# miniSpartan6__Rev_B.net
KiCad netlist of a schematic drawn in EAGLE
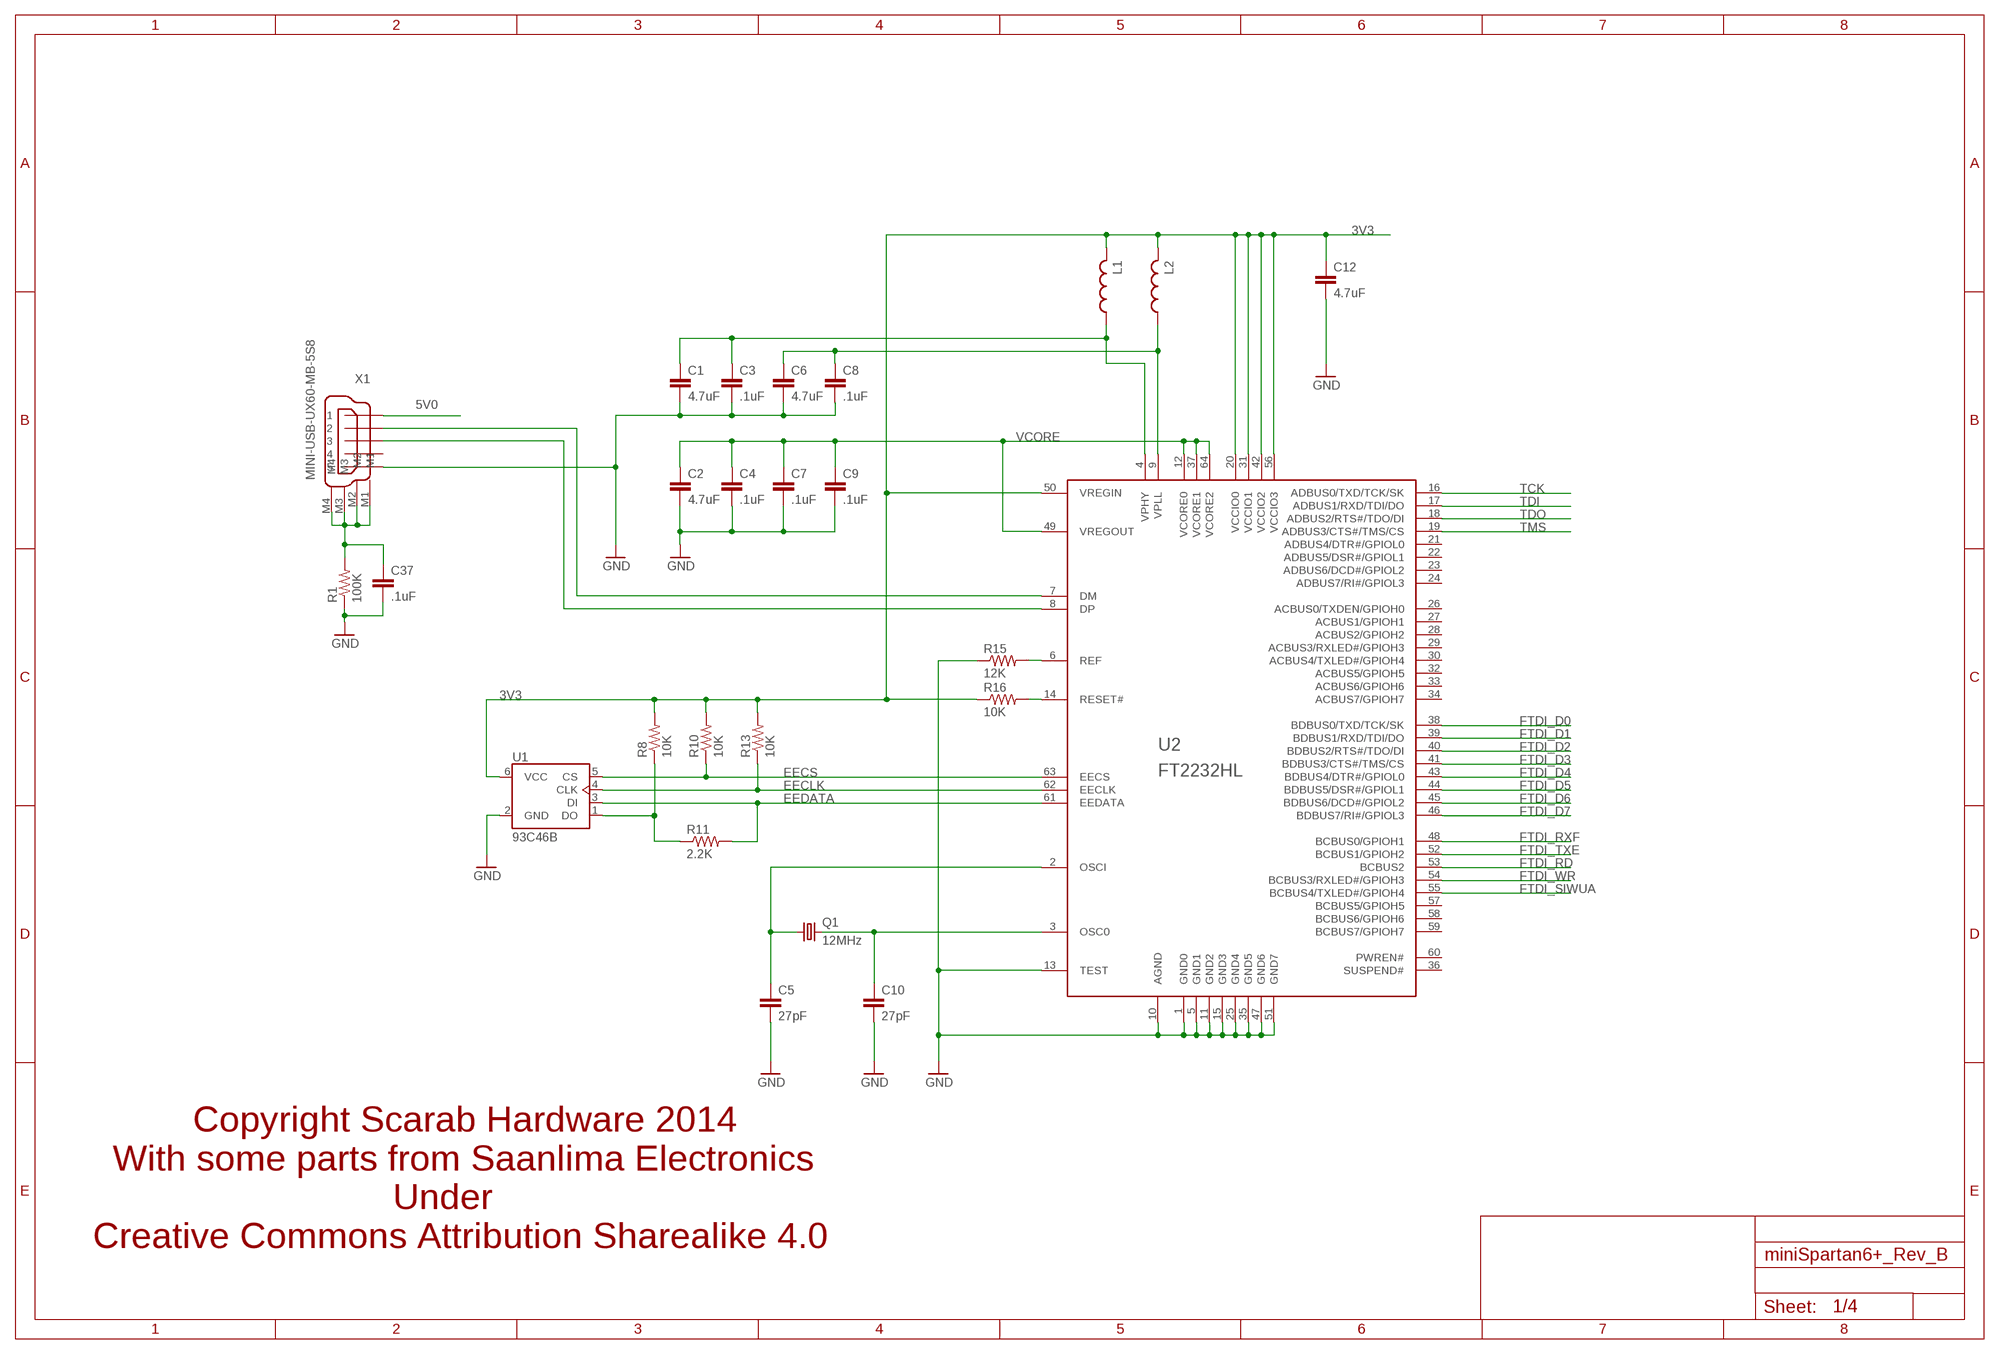
[diagram p0: schematic, sheet 1]
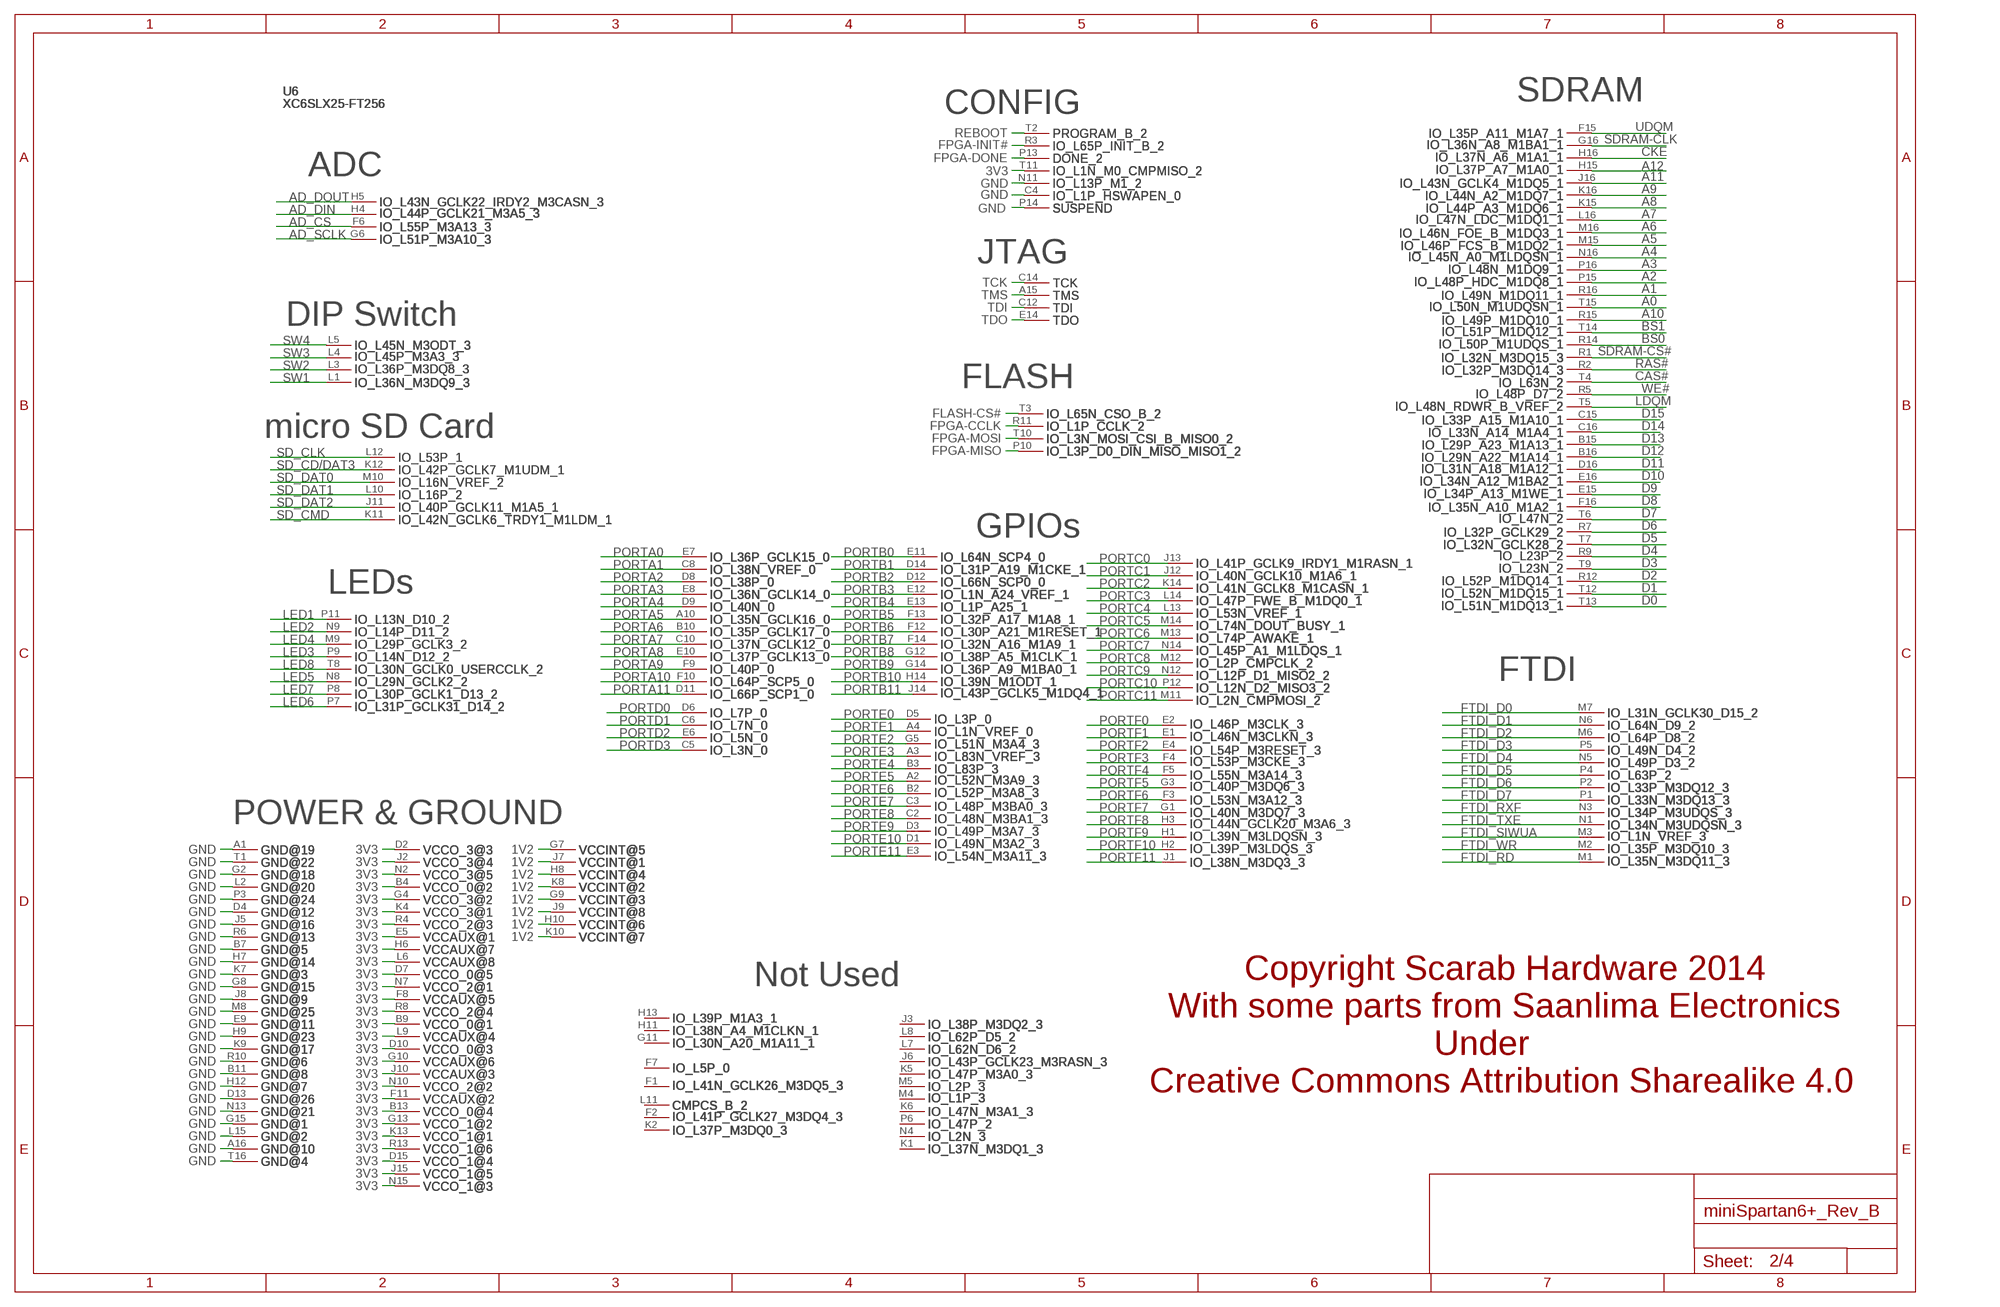
[diagram p1: schematic, sheet 2]
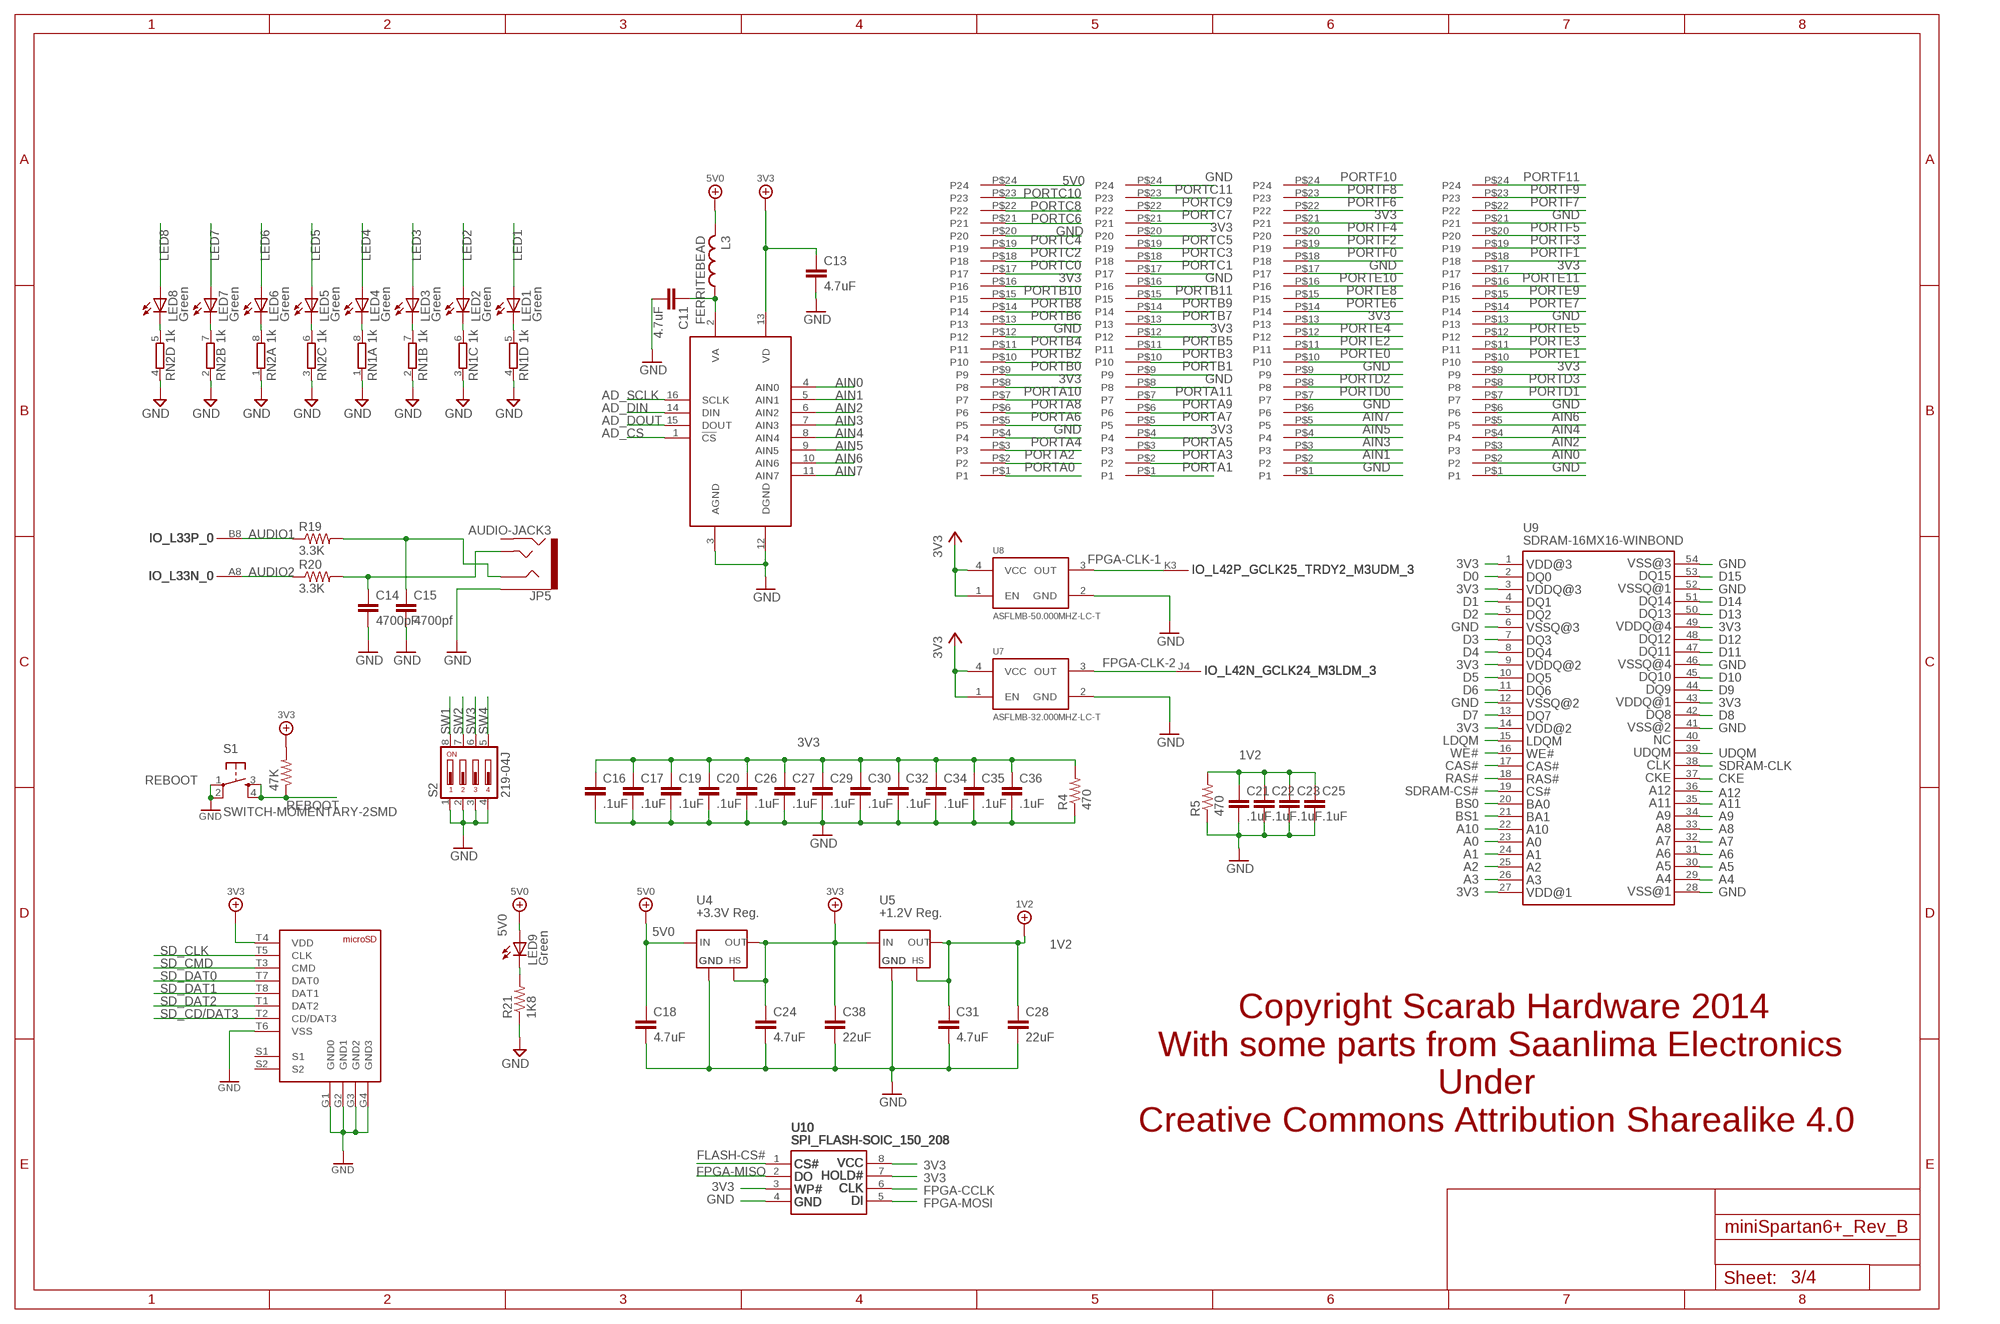
[diagram p2: schematic, sheet 3]
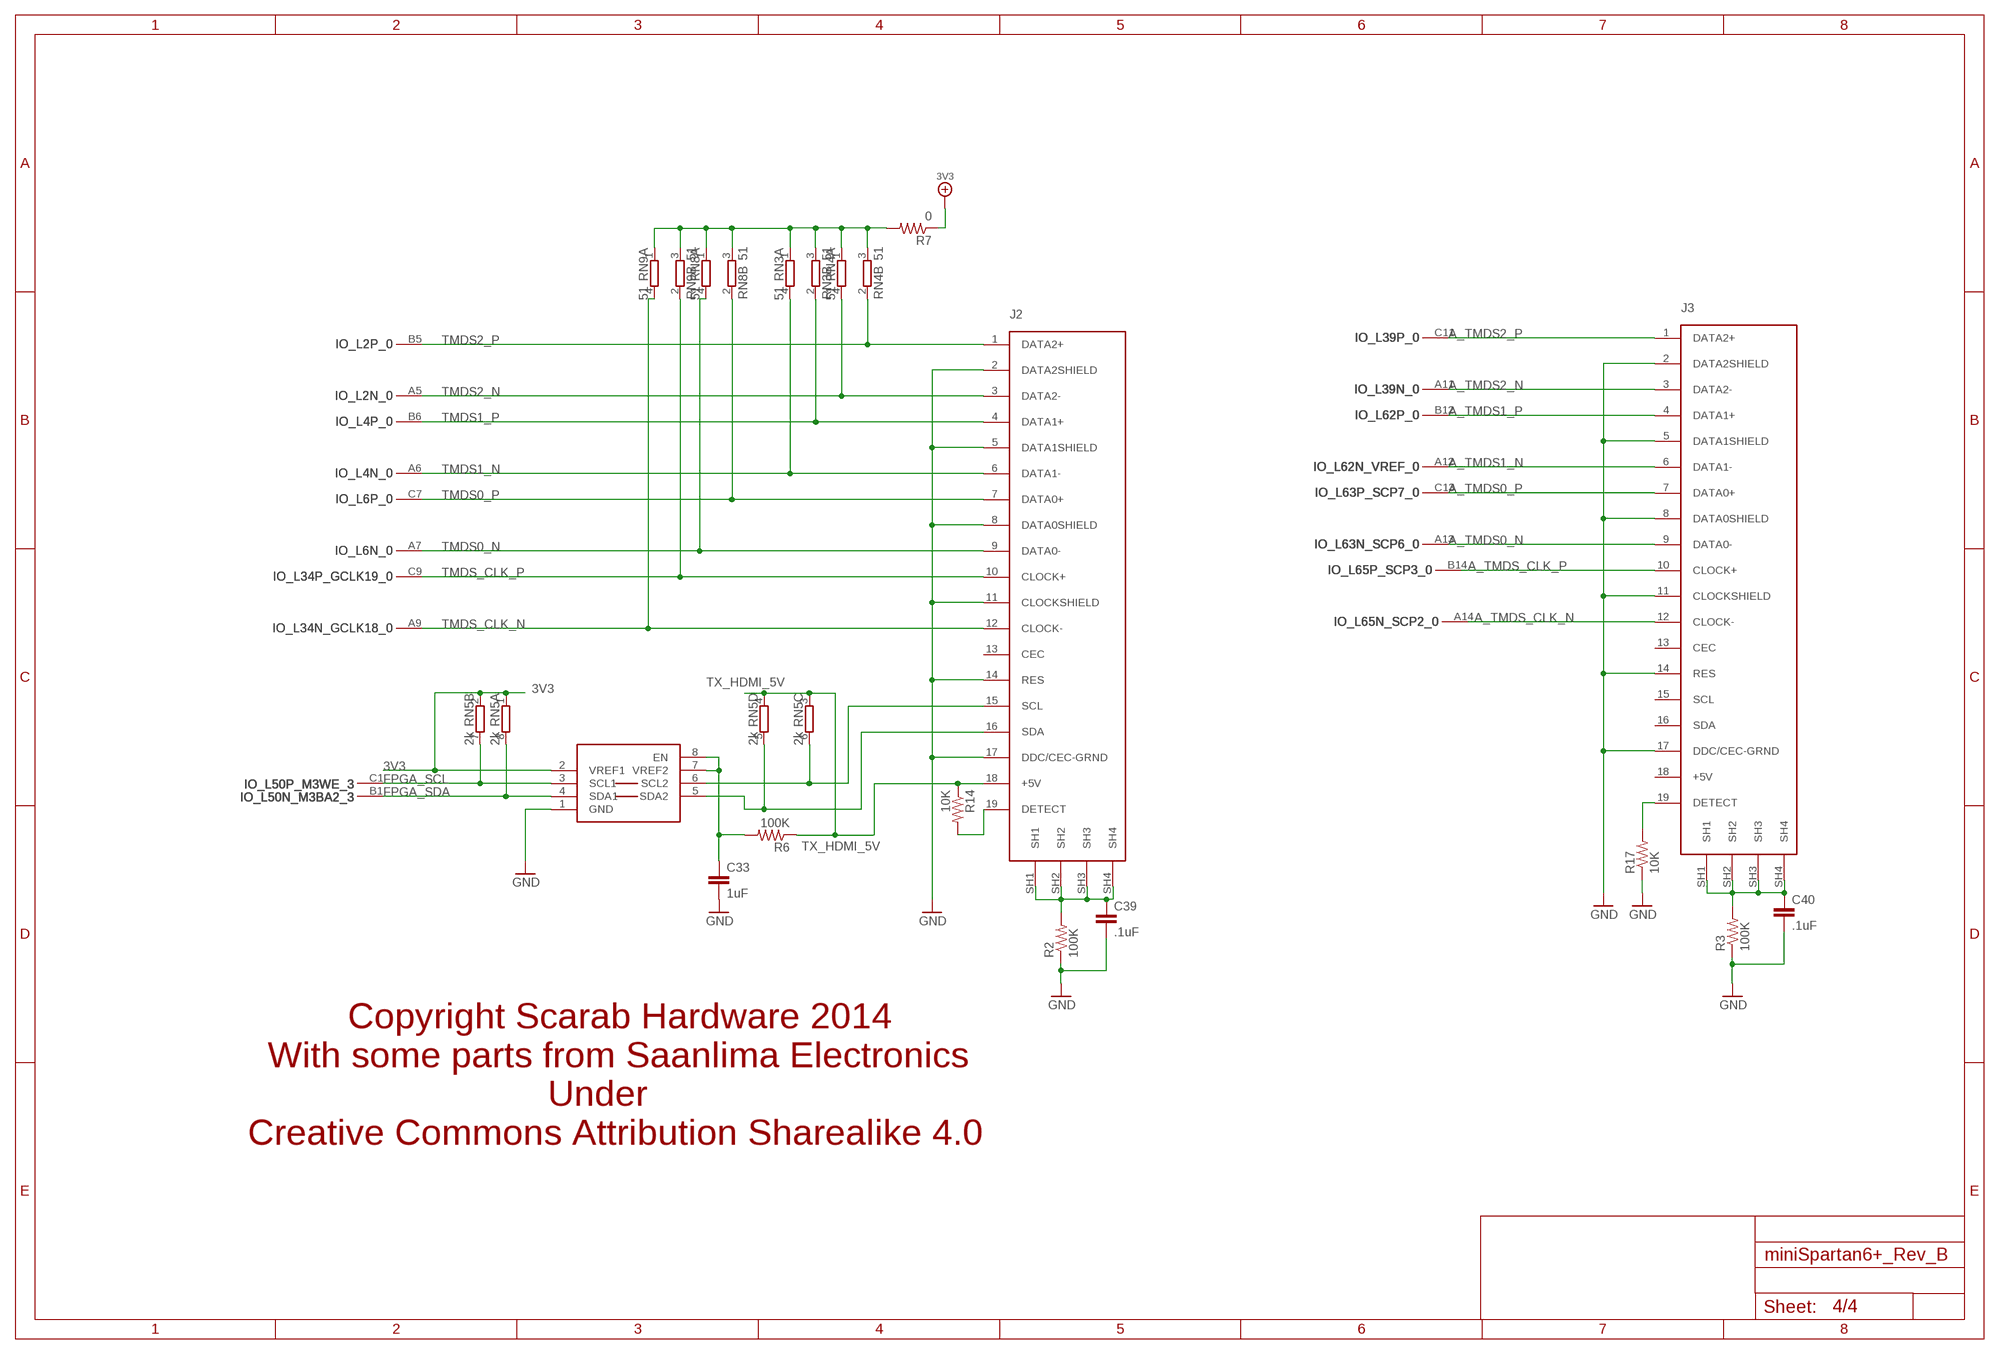
[diagram p3: schematic, sheet 4]

(export (version "E")
  (design (tool "Eeschema 10.0.6"))
  (components
    (comp (ref "C1")
      (value "4.7uF")
      (footprint "eagle-import:C0603K")
      (libsource (lib "eagle-import") (part "C-EUC0603K"))
    )
    (comp (ref "C2")
      (value "4.7uF")
      (footprint "eagle-import:C0603K")
      (libsource (lib "eagle-import") (part "C-EUC0603K"))
    )
    (comp (ref "C3")
      (value ".1uF")
      (footprint "eagle-import:C0603K")
      (libsource (lib "eagle-import") (part "C-EUC0603K"))
    )
    (comp (ref "C4")
      (value ".1uF")
      (footprint "eagle-import:C0603K")
      (libsource (lib "eagle-import") (part "C-EUC0603K"))
    )
    (comp (ref "C5")
      (value "27pF")
      (footprint "eagle-import:C0603K")
      (libsource (lib "eagle-import") (part "C-EUC0603K"))
    )
    (comp (ref "C6")
      (value "4.7uF")
      (footprint "eagle-import:C0603K")
      (libsource (lib "eagle-import") (part "C-EUC0603K"))
    )
    (comp (ref "C7")
      (value ".1uF")
      (footprint "eagle-import:C0603K")
      (libsource (lib "eagle-import") (part "C-EUC0603K"))
    )
    (comp (ref "C8")
      (value ".1uF")
      (footprint "eagle-import:C0603K")
      (libsource (lib "eagle-import") (part "C-EUC0603K"))
    )
    (comp (ref "C9")
      (value ".1uF")
      (footprint "eagle-import:C0603K")
      (libsource (lib "eagle-import") (part "C-EUC0603K"))
    )
    (comp (ref "C10")
      (value "27pF")
      (footprint "eagle-import:C0603K")
      (libsource (lib "eagle-import") (part "C-EUC0603K"))
    )
    (comp (ref "C12")
      (value "4.7uF")
      (footprint "eagle-import:C0603K")
      (libsource (lib "eagle-import") (part "C-EUC0603K"))
    )
    (comp (ref "C37")
      (value ".1uF")
      (footprint "eagle-import:C0603K")
      (libsource (lib "eagle-import") (part "C-EUC0603K"))
    )
    (comp (ref "L1")
      (value "L-USL2012C")
      (footprint "eagle-import:L2012C")
      (libsource (lib "eagle-import") (part "L-USL2012C"))
    )
    (comp (ref "L2")
      (value "L-USL2012C")
      (footprint "eagle-import:L2012C")
      (libsource (lib "eagle-import") (part "L-USL2012C"))
    )
    (comp (ref "Q1")
      (value "12MHz")
      (footprint "eagle-import:CRYSTAL3.2X2.5MM")
      (libsource (lib "eagle-import") (part "CRYSTAL3.2X2.5"))
    )
    (comp (ref "R1")
      (value "100K")
      (footprint "eagle-import:R0603")
      (libsource (lib "eagle-import") (part "R-US_R0603"))
    )
    (comp (ref "R8")
      (value "10K")
      (footprint "eagle-import:R0603")
      (libsource (lib "eagle-import") (part "R-US_R0603"))
    )
    (comp (ref "R10")
      (value "10K")
      (footprint "eagle-import:R0603")
      (libsource (lib "eagle-import") (part "R-US_R0603"))
    )
    (comp (ref "R11")
      (value "2.2K")
      (footprint "eagle-import:R0603")
      (libsource (lib "eagle-import") (part "R-US_R0603"))
    )
    (comp (ref "R13")
      (value "10K")
      (footprint "eagle-import:R0603")
      (libsource (lib "eagle-import") (part "R-US_R0603"))
    )
    (comp (ref "R15")
      (value "12K")
      (footprint "eagle-import:R0603")
      (libsource (lib "eagle-import") (part "R-US_R0603"))
    )
    (comp (ref "R16")
      (value "10K")
      (footprint "eagle-import:R0603")
      (libsource (lib "eagle-import") (part "R-US_R0603"))
    )
    (comp (ref "U1")
      (value "93C46B")
      (footprint "eagle-import:SOT23-6")
      (libsource (lib "eagle-import") (part "DIGITAL-EEPROM-MICROWIRE-6P_SOT23"))
    )
    (comp (ref "U2")
      (value "FT2232HL")
      (footprint "eagle-import:LQFP64")
      (libsource (lib "eagle-import") (part "FT2232H"))
    )
    (comp (ref "X1")
      (value "MINI-USB-UX60-MB-5S8")
      (footprint "eagle-import:UX60-MB-5S8")
      (libsource (lib "eagle-import") (part "MINI-USB-UX60-MB-5S8"))
    )
    (comp (ref "C33")
      (value "1uF")
      (footprint "eagle-import:C0603K")
      (libsource (lib "eagle-import") (part "C-EUC0603K"))
    )
    (comp (ref "C39")
      (value ".1uF")
      (footprint "eagle-import:C0603K")
      (libsource (lib "eagle-import") (part "C-EUC0603K"))
    )
    (comp (ref "C40")
      (value ".1uF")
      (footprint "eagle-import:C0603K")
      (libsource (lib "eagle-import") (part "C-EUC0603K"))
    )
    (comp (ref "J2")
      (value "HDMI-TYPE-A-RECEPTICALFCI10029449")
      (footprint "eagle-import:FCI-HDMI-TYPE-A-RECEPT")
      (libsource (lib "eagle-import") (part "HDMI-TYPE-A-RECEPTICALFCI10029449"))
    )
    (comp (ref "J3")
      (value "HDMI-TYPE-A-RECEPTICALFCI10029449")
      (footprint "eagle-import:FCI-HDMI-TYPE-A-RECEPT")
      (libsource (lib "eagle-import") (part "HDMI-TYPE-A-RECEPTICALFCI10029449"))
    )
    (comp (ref "R2")
      (value "100K")
      (footprint "eagle-import:R0603")
      (libsource (lib "eagle-import") (part "R-US_R0603"))
    )
    (comp (ref "R3")
      (value "100K")
      (footprint "eagle-import:R0603")
      (libsource (lib "eagle-import") (part "R-US_R0603"))
    )
    (comp (ref "R6")
      (value "100K")
      (footprint "eagle-import:R0603")
      (libsource (lib "eagle-import") (part "R-US_R0603"))
    )
    (comp (ref "R7")
      (value "0")
      (footprint "eagle-import:R0603")
      (libsource (lib "eagle-import") (part "R-US_R0603"))
    )
    (comp (ref "R14")
      (value "10K")
      (footprint "eagle-import:R0603")
      (libsource (lib "eagle-import") (part "R-US_R0603"))
    )
    (comp (ref "R17")
      (value "10K")
      (footprint "eagle-import:R0603")
      (libsource (lib "eagle-import") (part "R-US_R0603"))
    )
    (comp (ref "RN3")
      (value "51")
      (footprint "eagle-import:EXB34V")
      (libsource (lib "eagle-import") (part "2R-NEXB34V"))
    )
    (comp (ref "RN4")
      (value "51")
      (footprint "eagle-import:EXB34V")
      (libsource (lib "eagle-import") (part "2R-NEXB34V"))
    )
    (comp (ref "RN5")
      (value "2k")
      (footprint "eagle-import:0603-ARV")
      (libsource (lib "eagle-import") (part "4R-N0603-ARV"))
    )
    (comp (ref "RN8")
      (value "51")
      (footprint "eagle-import:EXB34V")
      (libsource (lib "eagle-import") (part "2R-NEXB34V"))
    )
    (comp (ref "RN9")
      (value "51")
      (footprint "eagle-import:EXB34V")
      (libsource (lib "eagle-import") (part "2R-NEXB34V"))
    )
    (comp (ref "U6")
      (value "XC6SLX25-FT256")
      (footprint "eagle-import:XILINX-FT256")
      (fields
        (field (name "DIGIKEY#") "122-1753-ND")
        (field (name "MANF") "XILINX")
        (field (name "MANF#") "XC6SLX25-2FTG256C")
      )
      (libsource (lib "eagle-import") (part "XC6SLX25-FT256"))
    )
    (comp (ref "U11")
      (value "PCA9306")
      (footprint "eagle-import:PSOP-8")
      (libsource (lib "eagle-import") (part "PCA9306"))
    )
    (comp (ref "C11")
      (value "4.7uF")
      (footprint "eagle-import:C0603K")
      (libsource (lib "eagle-import") (part "C-EUC0603K"))
    )
    (comp (ref "C13")
      (value "4.7uF")
      (footprint "eagle-import:C0603K")
      (libsource (lib "eagle-import") (part "C-EUC0603K"))
    )
    (comp (ref "C14")
      (value "4700pF")
      (footprint "eagle-import:C0603K")
      (libsource (lib "eagle-import") (part "C-EUC0603K"))
    )
    (comp (ref "C15")
      (value "4700pf")
      (footprint "eagle-import:C0603K")
      (libsource (lib "eagle-import") (part "C-EUC0603K"))
    )
    (comp (ref "C16")
      (value ".1uF")
      (footprint "eagle-import:C0603K")
      (libsource (lib "eagle-import") (part "C-EUC0603K"))
    )
    (comp (ref "C17")
      (value ".1uF")
      (footprint "eagle-import:C0603K")
      (libsource (lib "eagle-import") (part "C-EUC0603K"))
    )
    (comp (ref "C18")
      (value "4.7uF")
      (footprint "eagle-import:C0603K")
      (fields (field (name "MANF") "Murata"))
      (libsource (lib "eagle-import") (part "C-EUC0603K"))
    )
    (comp (ref "C19")
      (value ".1uF")
      (footprint "eagle-import:C0603K")
      (libsource (lib "eagle-import") (part "C-EUC0603K"))
    )
    (comp (ref "C20")
      (value ".1uF")
      (footprint "eagle-import:C0603K")
      (libsource (lib "eagle-import") (part "C-EUC0603K"))
    )
    (comp (ref "C21")
      (value ".1uF")
      (footprint "eagle-import:C0603K")
      (libsource (lib "eagle-import") (part "C-EUC0603K"))
    )
    (comp (ref "C22")
      (value ".1uF")
      (footprint "eagle-import:C0603K")
      (libsource (lib "eagle-import") (part "C-EUC0603K"))
    )
    (comp (ref "C23")
      (value ".1uF")
      (footprint "eagle-import:C0603K")
      (libsource (lib "eagle-import") (part "C-EUC0603K"))
    )
    (comp (ref "C24")
      (value "4.7uF")
      (footprint "eagle-import:C0603K")
      (fields (field (name "MANF") "Murata"))
      (libsource (lib "eagle-import") (part "C-EUC0603K"))
    )
    (comp (ref "C25")
      (value ".1uF")
      (footprint "eagle-import:C0603K")
      (libsource (lib "eagle-import") (part "C-EUC0603K"))
    )
    (comp (ref "C26")
      (value ".1uF")
      (footprint "eagle-import:C0603K")
      (libsource (lib "eagle-import") (part "C-EUC0603K"))
    )
    (comp (ref "C27")
      (value ".1uF")
      (footprint "eagle-import:C0603K")
      (libsource (lib "eagle-import") (part "C-EUC0603K"))
    )
    (comp (ref "C28")
      (value "22uF")
      (footprint "eagle-import:C0603K")
      (fields (field (name "MANF") "Murata"))
      (libsource (lib "eagle-import") (part "C-EUC0603K"))
    )
    (comp (ref "C29")
      (value ".1uF")
      (footprint "eagle-import:C0603K")
      (libsource (lib "eagle-import") (part "C-EUC0603K"))
    )
    (comp (ref "C30")
      (value ".1uF")
      (footprint "eagle-import:C0603K")
      (libsource (lib "eagle-import") (part "C-EUC0603K"))
    )
    (comp (ref "C31")
      (value "4.7uF")
      (footprint "eagle-import:C0603K")
      (fields (field (name "MANF") "Murata"))
      (libsource (lib "eagle-import") (part "C-EUC0603K"))
    )
    (comp (ref "C32")
      (value ".1uF")
      (footprint "eagle-import:C0603K")
      (libsource (lib "eagle-import") (part "C-EUC0603K"))
    )
    (comp (ref "C34")
      (value ".1uF")
      (footprint "eagle-import:C0603K")
      (libsource (lib "eagle-import") (part "C-EUC0603K"))
    )
    (comp (ref "C35")
      (value ".1uF")
      (footprint "eagle-import:C0603K")
      (libsource (lib "eagle-import") (part "C-EUC0603K"))
    )
    (comp (ref "C36")
      (value ".1uF")
      (footprint "eagle-import:C0603K")
      (libsource (lib "eagle-import") (part "C-EUC0603K"))
    )
    (comp (ref "C38")
      (value "22uF")
      (footprint "eagle-import:C0603K")
      (fields (field (name "MANF") "Murata"))
      (libsource (lib "eagle-import") (part "C-EUC0603K"))
    )
    (comp (ref "J4")
      (value "P24-1")
      (footprint "eagle-import:1X24")
      (libsource (lib "eagle-import") (part "P24-1"))
    )
    (comp (ref "J5")
      (value "MICROSD_MOLEX")
      (footprint "eagle-import:MICROSD_104031")
      (libsource (lib "eagle-import") (part "MICROSD_MOLEX"))
    )
    (comp (ref "J6")
      (value "P24-1")
      (footprint "eagle-import:1X24")
      (libsource (lib "eagle-import") (part "P24-1"))
    )
    (comp (ref "JP5")
      (value "AUDIO-JACK3")
      (footprint "eagle-import:AUDIO-JACK-TRRS-SMD")
      (libsource (lib "eagle-import") (part "AUDIO-JACK3"))
    )
    (comp (ref "L3")
      (value "FERRITEBEAD")
      (footprint "eagle-import:L2012C")
      (libsource (lib "eagle-import") (part "L-USL2012C"))
    )
    (comp (ref "LED1")
      (value "Green")
      (footprint "eagle-import:SML0603")
      (libsource (lib "eagle-import") (part "LEDSML0603"))
    )
    (comp (ref "LED2")
      (value "Green")
      (footprint "eagle-import:SML0603")
      (libsource (lib "eagle-import") (part "LEDSML0603"))
    )
    (comp (ref "LED3")
      (value "Green")
      (footprint "eagle-import:SML0603")
      (libsource (lib "eagle-import") (part "LEDSML0603"))
    )
    (comp (ref "LED4")
      (value "Green")
      (footprint "eagle-import:SML0603")
      (libsource (lib "eagle-import") (part "LEDSML0603"))
    )
    (comp (ref "LED5")
      (value "Green")
      (footprint "eagle-import:SML0603")
      (libsource (lib "eagle-import") (part "LEDSML0603"))
    )
    (comp (ref "LED6")
      (value "Green")
      (footprint "eagle-import:SML0603")
      (libsource (lib "eagle-import") (part "LEDSML0603"))
    )
    (comp (ref "LED7")
      (value "Green")
      (footprint "eagle-import:SML0603")
      (libsource (lib "eagle-import") (part "LEDSML0603"))
    )
    (comp (ref "LED8")
      (value "Green")
      (footprint "eagle-import:SML0603")
      (libsource (lib "eagle-import") (part "LEDSML0603"))
    )
    (comp (ref "LED9")
      (value "Green")
      (footprint "eagle-import:SML0603")
      (libsource (lib "eagle-import") (part "LEDSML0603"))
    )
    (comp (ref "R4")
      (value "470")
      (footprint "eagle-import:R0603")
      (libsource (lib "eagle-import") (part "R-US_R0603"))
    )
    (comp (ref "R5")
      (value "470")
      (footprint "eagle-import:R0603")
      (libsource (lib "eagle-import") (part "R-US_R0603"))
    )
    (comp (ref "R18")
      (value "47K")
      (footprint "eagle-import:R0603")
      (libsource (lib "eagle-import") (part "R-US_R0603"))
    )
    (comp (ref "R19")
      (value "3.3K")
      (footprint "eagle-import:R0603")
      (libsource (lib "eagle-import") (part "R-US_R0603"))
    )
    (comp (ref "R20")
      (value "3.3K")
      (footprint "eagle-import:R0603")
      (libsource (lib "eagle-import") (part "R-US_R0603"))
    )
    (comp (ref "R21")
      (value "1K8")
      (footprint "eagle-import:R0603")
      (libsource (lib "eagle-import") (part "R-US_R0603"))
    )
    (comp (ref "RN1")
      (value "1k")
      (footprint "eagle-import:0603-ARV")
      (libsource (lib "eagle-import") (part "4R-N0603-ARV"))
    )
    (comp (ref "RN2")
      (value "1k")
      (footprint "eagle-import:0603-ARV")
      (libsource (lib "eagle-import") (part "4R-N0603-ARV"))
    )
    (comp (ref "S1")
      (value "SWITCH-MOMENTARY-2SMD")
      (footprint "eagle-import:TACTILE_SWITCH_SMD")
      (libsource (lib "eagle-import") (part "TAC_SWITCHSMD"))
    )
    (comp (ref "S2")
      (value "219-04J")
      (footprint "eagle-import:CTS-219-04J")
      (libsource (lib "eagle-import") (part "219-04J"))
    )
    (comp (ref "U$7")
      (value "P24-1")
      (footprint "eagle-import:1X24")
      (libsource (lib "eagle-import") (part "P24-1"))
    )
    (comp (ref "U$8")
      (value "P24-1")
      (footprint "eagle-import:1X24")
      (libsource (lib "eagle-import") (part "P24-1"))
    )
    (comp (ref "U3")
      (value "ADC088S102CIMT")
      (footprint "eagle-import:TSSOP16")
      (libsource (lib "eagle-import") (part "ADC088S102CIMT"))
    )
    (comp (ref "U4")
      (value "+3.3V Reg.")
      (footprint "eagle-import:SOT223")
      (fields (field (name "MANF") "Diodes/Zetex"))
      (libsource (lib "eagle-import") (part "FAN1117"))
    )
    (comp (ref "U5")
      (value "+1.2V Reg.")
      (footprint "eagle-import:SOT223")
      (fields (field (name "MANF") "Diodes/Zetex"))
      (libsource (lib "eagle-import") (part "FAN1112"))
    )
    (comp (ref "U7")
      (value "ASFLMB-32.000MHZ-LC-T")
      (footprint "eagle-import:CRYSTAL-OSC-SMD-5X3")
      (libsource (lib "eagle-import") (part "OSCILLATOR5X3-PIN1-INDICATED"))
    )
    (comp (ref "U8")
      (value "ASFLMB-50.000MHZ-LC-T")
      (footprint "eagle-import:CRYSTAL-OSC-SMD-5X3")
      (libsource (lib "eagle-import") (part "OSCILLATOR5X3-PIN1-INDICATED"))
    )
    (comp (ref "U9")
      (value "SDRAM-16MX16-WINBOND")
      (footprint "eagle-import:TSOPII-54")
      (fields (field (name "MANF") "Winbond"))
      (libsource (lib "eagle-import") (part "SDRAM-16MX16-WINBOND"))
    )
    (comp (ref "U10")
      (value "SPI_FLASH-SOIC_150_208")
      (footprint "eagle-import:SPI-8_SOIC_150_208")
      (fields
        (field (name "MANF") "Winbond")
        (field (name "DIGIKEY#") "W25Q80BVSNIG-ND")
        (field (name "MANF_1") "Winbond")
        (field (name "MANF#") "W25Q80BVSNIG")
      )
      (libsource (lib "eagle-import") (part "SPI_FLASH-SOIC_150_208"))
    )
  )
  (nets
    (net (code "1") (name "1V2") (class "Default")
      (node (ref "C21") (pin "1") (pinfunction "1_1") (pintype "passive"))
      (node (ref "C22") (pin "1") (pinfunction "1_1") (pintype "passive"))
      (node (ref "C23") (pin "1") (pinfunction "1_1") (pintype "passive"))
      (node (ref "C25") (pin "1") (pinfunction "1_1") (pintype "passive"))
      (node (ref "C28") (pin "1") (pinfunction "1_1") (pintype "passive"))
      (node (ref "C31") (pin "1") (pinfunction "1_1") (pintype "passive"))
      (node (ref "R5") (pin "2") (pinfunction "2_2") (pintype "passive"))
      (node (ref "U5") (pin "2") (pinfunction "OUT_2") (pintype "passive"))
      (node (ref "U5") (pin "4") (pinfunction "HS_4") (pintype "passive"))
      (node (ref "U6") (pin "G7") (pinfunction "1_G7") (pintype "input"))
      (node (ref "U6") (pin "G9") (pinfunction "1_G9") (pintype "input"))
      (node (ref "U6") (pin "H10") (pinfunction "1_H10") (pintype "input"))
      (node (ref "U6") (pin "H8") (pinfunction "1_H8") (pintype "input"))
      (node (ref "U6") (pin "J7") (pinfunction "1_J7") (pintype "input"))
      (node (ref "U6") (pin "J9") (pinfunction "1_J9") (pintype "input"))
      (node (ref "U6") (pin "K10") (pinfunction "1_K10") (pintype "input"))
      (node (ref "U6") (pin "K8") (pinfunction "1_K8") (pintype "input"))
    )
    (net (code "2") (name "3V3") (class "Default")
      (node (ref "C12") (pin "1") (pinfunction "1_1") (pintype "passive"))
      (node (ref "C13") (pin "1") (pinfunction "1_1") (pintype "passive"))
      (node (ref "C16") (pin "1") (pinfunction "1_1") (pintype "passive"))
      (node (ref "C17") (pin "1") (pinfunction "1_1") (pintype "passive"))
      (node (ref "C19") (pin "1") (pinfunction "1_1") (pintype "passive"))
      (node (ref "C20") (pin "1") (pinfunction "1_1") (pintype "passive"))
      (node (ref "C24") (pin "1") (pinfunction "1_1") (pintype "passive"))
      (node (ref "C26") (pin "1") (pinfunction "1_1") (pintype "passive"))
      (node (ref "C27") (pin "1") (pinfunction "1_1") (pintype "passive"))
      (node (ref "C29") (pin "1") (pinfunction "1_1") (pintype "passive"))
      (node (ref "C30") (pin "1") (pinfunction "1_1") (pintype "passive"))
      (node (ref "C32") (pin "1") (pinfunction "1_1") (pintype "passive"))
      (node (ref "C34") (pin "1") (pinfunction "1_1") (pintype "passive"))
      (node (ref "C35") (pin "1") (pinfunction "1_1") (pintype "passive"))
      (node (ref "C36") (pin "1") (pinfunction "1_1") (pintype "passive"))
      (node (ref "C38") (pin "1") (pinfunction "1_1") (pintype "passive"))
      (node (ref "J4") (pin "P$13") (pinfunction "P13_P$13") (pintype "bidirectional"))
      (node (ref "J4") (pin "P$21") (pinfunction "P21_P$21") (pintype "bidirectional"))
      (node (ref "J5") (pin "T4") (pinfunction "VDD_T4") (pintype "bidirectional"))
      (node (ref "J6") (pin "P$17") (pinfunction "P17_P$17") (pintype "bidirectional"))
      (node (ref "J6") (pin "P$9") (pinfunction "P9_P$9") (pintype "bidirectional"))
      (node (ref "L1") (pin "2") (pinfunction "2_2") (pintype "passive"))
      (node (ref "L2") (pin "2") (pinfunction "2_2") (pintype "passive"))
      (node (ref "R10") (pin "2") (pinfunction "2_2") (pintype "passive"))
      (node (ref "R13") (pin "2") (pinfunction "2_2") (pintype "passive"))
      (node (ref "R16") (pin "1") (pinfunction "1_1") (pintype "passive"))
      (node (ref "R18") (pin "2") (pinfunction "2_2") (pintype "passive"))
      (node (ref "R4") (pin "2") (pinfunction "2_2") (pintype "passive"))
      (node (ref "R7") (pin "1") (pinfunction "1_1") (pintype "passive"))
      (node (ref "R8") (pin "2") (pinfunction "2_2") (pintype "passive"))
      (node (ref "RN5") (pin "1") (pinfunction "1_1") (pintype "passive"))
      (node (ref "RN5") (pin "2") (pinfunction "1_2") (pintype "passive"))
      (node (ref "U$7") (pin "P$16") (pinfunction "P16_P$16") (pintype "bidirectional"))
      (node (ref "U$7") (pin "P$8") (pinfunction "P8_P$8") (pintype "bidirectional"))
      (node (ref "U$8") (pin "P$12") (pinfunction "P12_P$12") (pintype "bidirectional"))
      (node (ref "U$8") (pin "P$20") (pinfunction "P20_P$20") (pintype "bidirectional"))
      (node (ref "U$8") (pin "P$4") (pinfunction "P4_P$4") (pintype "bidirectional"))
      (node (ref "U1") (pin "6") (pinfunction "VCC_6") (pintype "input"))
      (node (ref "U10") (pin "3") (pinfunction "1_3") (pintype "input"))
      (node (ref "U10") (pin "7") (pinfunction "1_7") (pintype "input"))
      (node (ref "U10") (pin "8") (pinfunction "1_8") (pintype "input"))
      (node (ref "U11") (pin "2") (pinfunction "VREF1_2") (pintype "bidirectional"))
      (node (ref "U2") (pin "20") (pinfunction "VCCIO0_20") (pintype "bidirectional"))
      (node (ref "U2") (pin "31") (pinfunction "VCCIO1_31") (pintype "bidirectional"))
      (node (ref "U2") (pin "42") (pinfunction "VCCIO2_42") (pintype "bidirectional"))
      (node (ref "U2") (pin "50") (pinfunction "VREGIN_50") (pintype "bidirectional"))
      (node (ref "U2") (pin "56") (pinfunction "VCCIO3_56") (pintype "bidirectional"))
      (node (ref "U3") (pin "13") (pinfunction "VD_13") (pintype "power_in"))
      (node (ref "U4") (pin "2") (pinfunction "OUT_2") (pintype "passive"))
      (node (ref "U4") (pin "4") (pinfunction "HS_4") (pintype "passive"))
      (node (ref "U5") (pin "3") (pinfunction "IN_3") (pintype "input"))
      (node (ref "U6") (pin "B13") (pinfunction "1_B13") (pintype "input"))
      (node (ref "U6") (pin "B4") (pinfunction "1_B4") (pintype "input"))
      (node (ref "U6") (pin "B9") (pinfunction "1_B9") (pintype "input"))
      (node (ref "U6") (pin "D10") (pinfunction "1_D10") (pintype "input"))
      (node (ref "U6") (pin "D15") (pinfunction "1_D15") (pintype "input"))
      (node (ref "U6") (pin "D2") (pinfunction "1_D2") (pintype "input"))
      (node (ref "U6") (pin "D7") (pinfunction "1_D7") (pintype "input"))
      (node (ref "U6") (pin "E5") (pinfunction "1_E5") (pintype "input"))
      (node (ref "U6") (pin "F11") (pinfunction "1_F11") (pintype "input"))
      (node (ref "U6") (pin "F8") (pinfunction "1_F8") (pintype "input"))
      (node (ref "U6") (pin "G10") (pinfunction "1_G10") (pintype "input"))
      (node (ref "U6") (pin "G13") (pinfunction "1_G13") (pintype "input"))
      (node (ref "U6") (pin "G4") (pinfunction "1_G4") (pintype "input"))
      (node (ref "U6") (pin "H6") (pinfunction "1_H6") (pintype "input"))
      (node (ref "U6") (pin "J10") (pinfunction "1_J10") (pintype "input"))
      (node (ref "U6") (pin "J15") (pinfunction "1_J15") (pintype "input"))
      (node (ref "U6") (pin "J2") (pinfunction "1_J2") (pintype "input"))
      (node (ref "U6") (pin "K13") (pinfunction "1_K13") (pintype "input"))
      (node (ref "U6") (pin "K4") (pinfunction "1_K4") (pintype "input"))
      (node (ref "U6") (pin "L6") (pinfunction "1_L6") (pintype "input"))
      (node (ref "U6") (pin "L9") (pinfunction "1_L9") (pintype "input"))
      (node (ref "U6") (pin "N10") (pinfunction "1_N10") (pintype "input"))
      (node (ref "U6") (pin "N15") (pinfunction "1_N15") (pintype "input"))
      (node (ref "U6") (pin "N2") (pinfunction "1_N2") (pintype "input"))
      (node (ref "U6") (pin "N7") (pinfunction "1_N7") (pintype "input"))
      (node (ref "U6") (pin "R13") (pinfunction "1_R13") (pintype "input"))
      (node (ref "U6") (pin "R4") (pinfunction "1_R4") (pintype "input"))
      (node (ref "U6") (pin "R8") (pinfunction "1_R8") (pintype "input"))
      (node (ref "U6") (pin "T11") (pinfunction "1_T11") (pintype "bidirectional"))
      (node (ref "U7") (pin "1") (pinfunction "EN_1") (pintype "bidirectional"))
      (node (ref "U7") (pin "4") (pinfunction "VCC_4") (pintype "bidirectional"))
      (node (ref "U8") (pin "1") (pinfunction "EN_1") (pintype "bidirectional"))
      (node (ref "U8") (pin "4") (pinfunction "VCC_4") (pintype "bidirectional"))
      (node (ref "U9") (pin "1") (pinfunction "P$1_1") (pintype "bidirectional"))
      (node (ref "U9") (pin "14") (pinfunction "P$1_14") (pintype "bidirectional"))
      (node (ref "U9") (pin "27") (pinfunction "P$1_27") (pintype "bidirectional"))
      (node (ref "U9") (pin "3") (pinfunction "P$1_3") (pintype "bidirectional"))
      (node (ref "U9") (pin "43") (pinfunction "P$1_43") (pintype "bidirectional"))
      (node (ref "U9") (pin "49") (pinfunction "P$1_49") (pintype "bidirectional"))
      (node (ref "U9") (pin "9") (pinfunction "P$1_9") (pintype "bidirectional"))
    )
    (net (code "3") (name "5V0") (class "Default")
      (node (ref "C18") (pin "1") (pinfunction "1_1") (pintype "passive"))
      (node (ref "L3") (pin "2") (pinfunction "2_2") (pintype "passive"))
      (node (ref "LED9") (pin "A") (pinfunction "A_A") (pintype "passive"))
      (node (ref "U$7") (pin "P$24") (pinfunction "P24_P$24") (pintype "bidirectional"))
      (node (ref "U4") (pin "3") (pinfunction "IN_3") (pintype "input"))
      (node (ref "X1") (pin "1") (pinfunction "1_1") (pintype "input"))
    )
    (net (code "4") (name "A0") (class "Default")
      (node (ref "U6") (pin "T15") (pinfunction "1_T15") (pintype "bidirectional"))
      (node (ref "U9") (pin "23") (pinfunction "P$1_23") (pintype "bidirectional"))
    )
    (net (code "5") (name "A1") (class "Default")
      (node (ref "U6") (pin "R16") (pinfunction "1_R16") (pintype "bidirectional"))
      (node (ref "U9") (pin "24") (pinfunction "P$1_24") (pintype "bidirectional"))
    )
    (net (code "6") (name "A2") (class "Default")
      (node (ref "U6") (pin "P15") (pinfunction "1_P15") (pintype "bidirectional"))
      (node (ref "U9") (pin "25") (pinfunction "P$1_25") (pintype "bidirectional"))
    )
    (net (code "7") (name "A3") (class "Default")
      (node (ref "U6") (pin "P16") (pinfunction "1_P16") (pintype "bidirectional"))
      (node (ref "U9") (pin "26") (pinfunction "P$1_26") (pintype "bidirectional"))
    )
    (net (code "8") (name "A4") (class "Default")
      (node (ref "U6") (pin "N16") (pinfunction "1_N16") (pintype "bidirectional"))
      (node (ref "U9") (pin "29") (pinfunction "P$1_29") (pintype "bidirectional"))
    )
    (net (code "9") (name "A5") (class "Default")
      (node (ref "U6") (pin "M15") (pinfunction "1_M15") (pintype "bidirectional"))
      (node (ref "U9") (pin "30") (pinfunction "P$1_30") (pintype "bidirectional"))
    )
    (net (code "10") (name "A6") (class "Default")
      (node (ref "U6") (pin "M16") (pinfunction "1_M16") (pintype "bidirectional"))
      (node (ref "U9") (pin "31") (pinfunction "P$1_31") (pintype "bidirectional"))
    )
    (net (code "11") (name "A7") (class "Default")
      (node (ref "U6") (pin "L16") (pinfunction "1_L16") (pintype "bidirectional"))
      (node (ref "U9") (pin "32") (pinfunction "P$1_32") (pintype "bidirectional"))
    )
    (net (code "12") (name "A8") (class "Default")
      (node (ref "U6") (pin "K15") (pinfunction "1_K15") (pintype "bidirectional"))
      (node (ref "U9") (pin "33") (pinfunction "P$1_33") (pintype "bidirectional"))
    )
    (net (code "13") (name "A9") (class "Default")
      (node (ref "U6") (pin "K16") (pinfunction "1_K16") (pintype "bidirectional"))
      (node (ref "U9") (pin "34") (pinfunction "P$1_34") (pintype "bidirectional"))
    )
    (net (code "14") (name "A10") (class "Default")
      (node (ref "U6") (pin "R15") (pinfunction "1_R15") (pintype "bidirectional"))
      (node (ref "U9") (pin "22") (pinfunction "P$1_22") (pintype "bidirectional"))
    )
    (net (code "15") (name "A11") (class "Default")
      (node (ref "U6") (pin "J16") (pinfunction "1_J16") (pintype "bidirectional"))
      (node (ref "U9") (pin "35") (pinfunction "P$1_35") (pintype "bidirectional"))
    )
    (net (code "16") (name "A12") (class "Default")
      (node (ref "U6") (pin "H15") (pinfunction "1_H15") (pintype "bidirectional"))
      (node (ref "U9") (pin "36") (pinfunction "P$1_36") (pintype "bidirectional"))
    )
    (net (code "17") (name "AD_CS") (class "Default")
      (node (ref "U3") (pin "1") (pinfunction "~{CS}_1") (pintype "input"))
      (node (ref "U6") (pin "F6") (pinfunction "1_F6") (pintype "bidirectional"))
    )
    (net (code "18") (name "AD_DIN") (class "Default")
      (node (ref "U3") (pin "14") (pinfunction "DIN_14") (pintype "input"))
      (node (ref "U6") (pin "H4") (pinfunction "1_H4") (pintype "bidirectional"))
    )
    (net (code "19") (name "AD_DOUT") (class "Default")
      (node (ref "U3") (pin "15") (pinfunction "DOUT_15") (pintype "output"))
      (node (ref "U6") (pin "H5") (pinfunction "1_H5") (pintype "bidirectional"))
    )
    (net (code "20") (name "AD_SCLK") (class "Default")
      (node (ref "U3") (pin "16") (pinfunction "SCLK_16") (pintype "input"))
      (node (ref "U6") (pin "G6") (pinfunction "1_G6") (pintype "bidirectional"))
    )
    (net (code "21") (name "AIN0") (class "Default")
      (node (ref "J6") (pin "P$2") (pinfunction "P2_P$2") (pintype "bidirectional"))
      (node (ref "U3") (pin "4") (pinfunction "AIN0_4") (pintype "input"))
    )
    (net (code "22") (name "AIN1") (class "Default")
      (node (ref "J4") (pin "P$2") (pinfunction "P2_P$2") (pintype "bidirectional"))
      (node (ref "U3") (pin "5") (pinfunction "AIN1_5") (pintype "input"))
    )
    (net (code "23") (name "AIN2") (class "Default")
      (node (ref "J6") (pin "P$3") (pinfunction "P3_P$3") (pintype "bidirectional"))
      (node (ref "U3") (pin "6") (pinfunction "AIN2_6") (pintype "input"))
    )
    (net (code "24") (name "AIN3") (class "Default")
      (node (ref "J4") (pin "P$3") (pinfunction "P3_P$3") (pintype "bidirectional"))
      (node (ref "U3") (pin "7") (pinfunction "AIN3_7") (pintype "input"))
    )
    (net (code "25") (name "AIN4") (class "Default")
      (node (ref "J6") (pin "P$4") (pinfunction "P4_P$4") (pintype "bidirectional"))
      (node (ref "U3") (pin "8") (pinfunction "AIN4_8") (pintype "input"))
    )
    (net (code "26") (name "AIN5") (class "Default")
      (node (ref "J4") (pin "P$4") (pinfunction "P4_P$4") (pintype "bidirectional"))
      (node (ref "U3") (pin "9") (pinfunction "AIN5_9") (pintype "input"))
    )
    (net (code "27") (name "AIN6") (class "Default")
      (node (ref "J6") (pin "P$5") (pinfunction "P5_P$5") (pintype "bidirectional"))
      (node (ref "U3") (pin "10") (pinfunction "AIN6_10") (pintype "input"))
    )
    (net (code "28") (name "AIN7") (class "Default")
      (node (ref "J4") (pin "P$5") (pinfunction "P5_P$5") (pintype "bidirectional"))
      (node (ref "U3") (pin "11") (pinfunction "AIN7_11") (pintype "input"))
    )
    (net (code "29") (name "AUDIO1") (class "Default")
      (node (ref "R19") (pin "1") (pinfunction "1_1") (pintype "passive"))
      (node (ref "U6") (pin "B8") (pinfunction "1_B8") (pintype "bidirectional"))
    )
    (net (code "30") (name "AUDIO2") (class "Default")
      (node (ref "R20") (pin "1") (pinfunction "1_1") (pintype "passive"))
      (node (ref "U6") (pin "A8") (pinfunction "1_A8") (pintype "bidirectional"))
    )
    (net (code "31") (name "A_TMDS0_N") (class "Default")
      (node (ref "J3") (pin "9") (pinfunction "DATA0-_9") (pintype "bidirectional"))
      (node (ref "U6") (pin "A13") (pinfunction "1_A13") (pintype "bidirectional"))
    )
    (net (code "32") (name "A_TMDS0_P") (class "Default")
      (node (ref "J3") (pin "7") (pinfunction "DATA0+_7") (pintype "bidirectional"))
      (node (ref "U6") (pin "C13") (pinfunction "1_C13") (pintype "bidirectional"))
    )
    (net (code "33") (name "A_TMDS1_N") (class "Default")
      (node (ref "J3") (pin "6") (pinfunction "DATA1-_6") (pintype "bidirectional"))
      (node (ref "U6") (pin "A12") (pinfunction "1_A12") (pintype "bidirectional"))
    )
    (net (code "34") (name "A_TMDS1_P") (class "Default")
      (node (ref "J3") (pin "4") (pinfunction "DATA1+_4") (pintype "bidirectional"))
      (node (ref "U6") (pin "B12") (pinfunction "1_B12") (pintype "bidirectional"))
    )
    (net (code "35") (name "A_TMDS2_N") (class "Default")
      (node (ref "J3") (pin "3") (pinfunction "DATA2-_3") (pintype "bidirectional"))
      (node (ref "U6") (pin "A11") (pinfunction "1_A11") (pintype "bidirectional"))
    )
    (net (code "36") (name "A_TMDS2_P") (class "Default")
      (node (ref "J3") (pin "1") (pinfunction "DATA2+_1") (pintype "bidirectional"))
      (node (ref "U6") (pin "C11") (pinfunction "1_C11") (pintype "bidirectional"))
    )
    (net (code "37") (name "A_TMDS_CLK_N") (class "Default")
      (node (ref "J3") (pin "12") (pinfunction "CLOCK-_12") (pintype "bidirectional"))
      (node (ref "U6") (pin "A14") (pinfunction "1_A14") (pintype "bidirectional"))
    )
    (net (code "38") (name "A_TMDS_CLK_P") (class "Default")
      (node (ref "J3") (pin "10") (pinfunction "CLOCK+_10") (pintype "bidirectional"))
      (node (ref "U6") (pin "B14") (pinfunction "1_B14") (pintype "bidirectional"))
    )
    (net (code "39") (name "BS0") (class "Default")
      (node (ref "U6") (pin "R14") (pinfunction "1_R14") (pintype "bidirectional"))
      (node (ref "U9") (pin "20") (pinfunction "P$1_20") (pintype "bidirectional"))
    )
    (net (code "40") (name "BS1") (class "Default")
      (node (ref "U6") (pin "T14") (pinfunction "1_T14") (pintype "bidirectional"))
      (node (ref "U9") (pin "21") (pinfunction "P$1_21") (pintype "bidirectional"))
    )
    (net (code "41") (name "CAS#") (class "Default")
      (node (ref "U6") (pin "T4") (pinfunction "1_T4") (pintype "bidirectional"))
      (node (ref "U9") (pin "17") (pinfunction "P$1_17") (pintype "bidirectional"))
    )
    (net (code "42") (name "CKE") (class "Default")
      (node (ref "U6") (pin "H16") (pinfunction "1_H16") (pintype "bidirectional"))
      (node (ref "U9") (pin "37") (pinfunction "P$1_37") (pintype "bidirectional"))
    )
    (net (code "43") (name "D0") (class "Default")
      (node (ref "U6") (pin "T13") (pinfunction "1_T13") (pintype "bidirectional"))
      (node (ref "U9") (pin "2") (pinfunction "P$1_2") (pintype "bidirectional"))
    )
    (net (code "44") (name "D1") (class "Default")
      (node (ref "U6") (pin "T12") (pinfunction "1_T12") (pintype "bidirectional"))
      (node (ref "U9") (pin "4") (pinfunction "P$1_4") (pintype "bidirectional"))
    )
    (net (code "45") (name "D2") (class "Default")
      (node (ref "U6") (pin "R12") (pinfunction "1_R12") (pintype "bidirectional"))
      (node (ref "U9") (pin "5") (pinfunction "P$1_5") (pintype "bidirectional"))
    )
    (net (code "46") (name "D3") (class "Default")
      (node (ref "U6") (pin "T9") (pinfunction "1_T9") (pintype "bidirectional"))
      (node (ref "U9") (pin "7") (pinfunction "P$1_7") (pintype "bidirectional"))
    )
    (net (code "47") (name "D4") (class "Default")
      (node (ref "U6") (pin "R9") (pinfunction "1_R9") (pintype "bidirectional"))
      (node (ref "U9") (pin "8") (pinfunction "P$1_8") (pintype "bidirectional"))
    )
    (net (code "48") (name "D5") (class "Default")
      (node (ref "U6") (pin "T7") (pinfunction "1_T7") (pintype "bidirectional"))
      (node (ref "U9") (pin "10") (pinfunction "P$1_10") (pintype "bidirectional"))
    )
    (net (code "49") (name "D6") (class "Default")
      (node (ref "U6") (pin "R7") (pinfunction "1_R7") (pintype "bidirectional"))
      (node (ref "U9") (pin "11") (pinfunction "P$1_11") (pintype "bidirectional"))
    )
    (net (code "50") (name "D7") (class "Default")
      (node (ref "U6") (pin "T6") (pinfunction "1_T6") (pintype "bidirectional"))
      (node (ref "U9") (pin "13") (pinfunction "P$1_13") (pintype "bidirectional"))
    )
    (net (code "51") (name "D8") (class "Default")
      (node (ref "U6") (pin "F16") (pinfunction "1_F16") (pintype "bidirectional"))
      (node (ref "U9") (pin "42") (pinfunction "P$1_42") (pintype "bidirectional"))
    )
    (net (code "52") (name "D9") (class "Default")
      (node (ref "U6") (pin "E15") (pinfunction "1_E15") (pintype "bidirectional"))
      (node (ref "U9") (pin "44") (pinfunction "P$1_44") (pintype "bidirectional"))
    )
    (net (code "53") (name "D10") (class "Default")
      (node (ref "U6") (pin "E16") (pinfunction "1_E16") (pintype "bidirectional"))
      (node (ref "U9") (pin "45") (pinfunction "P$1_45") (pintype "bidirectional"))
    )
    (net (code "54") (name "D11") (class "Default")
      (node (ref "U6") (pin "D16") (pinfunction "1_D16") (pintype "bidirectional"))
      (node (ref "U9") (pin "47") (pinfunction "P$1_47") (pintype "bidirectional"))
    )
    (net (code "55") (name "D12") (class "Default")
      (node (ref "U6") (pin "B16") (pinfunction "1_B16") (pintype "bidirectional"))
      (node (ref "U9") (pin "48") (pinfunction "P$1_48") (pintype "bidirectional"))
    )
    (net (code "56") (name "D13") (class "Default")
      (node (ref "U6") (pin "B15") (pinfunction "1_B15") (pintype "bidirectional"))
      (node (ref "U9") (pin "50") (pinfunction "P$1_50") (pintype "bidirectional"))
    )
    (net (code "57") (name "D14") (class "Default")
      (node (ref "U6") (pin "C16") (pinfunction "1_C16") (pintype "bidirectional"))
      (node (ref "U9") (pin "51") (pinfunction "P$1_51") (pintype "bidirectional"))
    )
    (net (code "58") (name "D15") (class "Default")
      (node (ref "U6") (pin "C15") (pinfunction "1_C15") (pintype "bidirectional"))
      (node (ref "U9") (pin "53") (pinfunction "P$1_53") (pintype "bidirectional"))
    )
    (net (code "59") (name "EECLK") (class "Default")
      (node (ref "R13") (pin "1") (pinfunction "1_1") (pintype "passive"))
      (node (ref "U1") (pin "4") (pinfunction "CLK_4") (pintype "input"))
      (node (ref "U2") (pin "62") (pinfunction "EECLK_62") (pintype "bidirectional"))
    )
    (net (code "60") (name "EECS") (class "Default")
      (node (ref "R10") (pin "1") (pinfunction "1_1") (pintype "passive"))
      (node (ref "U1") (pin "5") (pinfunction "CS_5") (pintype "input"))
      (node (ref "U2") (pin "63") (pinfunction "EECS_63") (pintype "bidirectional"))
    )
    (net (code "61") (name "EEDATA") (class "Default")
      (node (ref "R11") (pin "2") (pinfunction "2_2") (pintype "passive"))
      (node (ref "U1") (pin "3") (pinfunction "DI_3") (pintype "input"))
      (node (ref "U2") (pin "61") (pinfunction "EEDATA_61") (pintype "bidirectional"))
    )
    (net (code "62") (name "FLASH-CS#") (class "Default")
      (node (ref "U10") (pin "1") (pinfunction "1_1") (pintype "input"))
      (node (ref "U6") (pin "T3") (pinfunction "1_T3") (pintype "bidirectional"))
    )
    (net (code "63") (name "FPGA-CCLK") (class "Default")
      (node (ref "U10") (pin "6") (pinfunction "1_6") (pintype "input"))
      (node (ref "U6") (pin "R11") (pinfunction "1_R11") (pintype "bidirectional"))
    )
    (net (code "64") (name "FPGA-CLK-1") (class "Default")
      (node (ref "U6") (pin "K3") (pinfunction "1_K3") (pintype "bidirectional"))
      (node (ref "U8") (pin "3") (pinfunction "OUT_3") (pintype "bidirectional"))
    )
    (net (code "65") (name "FPGA-CLK-2") (class "Default")
      (node (ref "U6") (pin "J4") (pinfunction "1_J4") (pintype "bidirectional"))
      (node (ref "U7") (pin "3") (pinfunction "OUT_3") (pintype "bidirectional"))
    )
    (net (code "66") (name "FPGA-DONE") (class "Default")
      (node (ref "U6") (pin "P13") (pinfunction "1_P13") (pintype "output"))
    )
    (net (code "67") (name "FPGA-INIT#") (class "Default")
      (node (ref "U6") (pin "R3") (pinfunction "1_R3") (pintype "bidirectional"))
    )
    (net (code "68") (name "FPGA-MISO") (class "Default")
      (node (ref "U10") (pin "2") (pinfunction "1_2") (pintype "output"))
      (node (ref "U6") (pin "P10") (pinfunction "1_P10") (pintype "bidirectional"))
    )
    (net (code "69") (name "FPGA-MOSI") (class "Default")
      (node (ref "U10") (pin "5") (pinfunction "1_5") (pintype "input"))
      (node (ref "U6") (pin "T10") (pinfunction "1_T10") (pintype "bidirectional"))
    )
    (net (code "70") (name "FPGA_SCL") (class "Default")
      (node (ref "RN5") (pin "7") (pinfunction "2_7") (pintype "passive"))
      (node (ref "U11") (pin "3") (pinfunction "SCL1_3") (pintype "bidirectional"))
      (node (ref "U6") (pin "C1") (pinfunction "1_C1") (pintype "bidirectional"))
    )
    (net (code "71") (name "FPGA_SDA") (class "Default")
      (node (ref "RN5") (pin "8") (pinfunction "2_8") (pintype "passive"))
      (node (ref "U11") (pin "4") (pinfunction "SDA1_4") (pintype "bidirectional"))
      (node (ref "U6") (pin "B1") (pinfunction "1_B1") (pintype "bidirectional"))
    )
    (net (code "72") (name "FTDI_D0") (class "Default")
      (node (ref "U2") (pin "38") (pinfunction "BDBUS0/TXD/TCK/SK_38") (pintype "bidirectional"))
      (node (ref "U6") (pin "M7") (pinfunction "1_M7") (pintype "bidirectional"))
    )
    (net (code "73") (name "FTDI_D1") (class "Default")
      (node (ref "U2") (pin "39") (pinfunction "BDBUS1/RXD/TDI/DO_39") (pintype "bidirectional"))
      (node (ref "U6") (pin "N6") (pinfunction "1_N6") (pintype "bidirectional"))
    )
    (net (code "74") (name "FTDI_D2") (class "Default")
      (node (ref "U2") (pin "40") (pinfunction "BDBUS2/RTS#/TDO/DI_40") (pintype "bidirectional"))
      (node (ref "U6") (pin "M6") (pinfunction "1_M6") (pintype "bidirectional"))
    )
    (net (code "75") (name "FTDI_D3") (class "Default")
      (node (ref "U2") (pin "41") (pinfunction "BDBUS3/CTS#/TMS/CS_41") (pintype "bidirectional"))
      (node (ref "U6") (pin "P5") (pinfunction "1_P5") (pintype "bidirectional"))
    )
    (net (code "76") (name "FTDI_D4") (class "Default")
      (node (ref "U2") (pin "43") (pinfunction "BDBUS4/DTR#/GPIOL0_43") (pintype "bidirectional"))
      (node (ref "U6") (pin "N5") (pinfunction "1_N5") (pintype "bidirectional"))
    )
    (net (code "77") (name "FTDI_D5") (class "Default")
      (node (ref "U2") (pin "44") (pinfunction "BDBUS5/DSR#/GPIOL1_44") (pintype "bidirectional"))
      (node (ref "U6") (pin "P4") (pinfunction "1_P4") (pintype "bidirectional"))
    )
    (net (code "78") (name "FTDI_D6") (class "Default")
      (node (ref "U2") (pin "45") (pinfunction "BDBUS6/DCD#/GPIOL2_45") (pintype "bidirectional"))
      (node (ref "U6") (pin "P2") (pinfunction "1_P2") (pintype "bidirectional"))
    )
    (net (code "79") (name "FTDI_D7") (class "Default")
      (node (ref "U2") (pin "46") (pinfunction "BDBUS7/RI#/GPIOL3_46") (pintype "bidirectional"))
      (node (ref "U6") (pin "P1") (pinfunction "1_P1") (pintype "bidirectional"))
    )
    (net (code "80") (name "FTDI_RD") (class "Default")
      (node (ref "U2") (pin "53") (pinfunction "BCBUS2_53") (pintype "bidirectional"))
      (node (ref "U6") (pin "M1") (pinfunction "1_M1") (pintype "bidirectional"))
    )
    (net (code "81") (name "FTDI_RXF") (class "Default")
      (node (ref "U2") (pin "48") (pinfunction "BCBUS0/GPIOH1_48") (pintype "bidirectional"))
      (node (ref "U6") (pin "N3") (pinfunction "1_N3") (pintype "bidirectional"))
    )
    (net (code "82") (name "FTDI_SIWUA") (class "Default")
      (node (ref "U2") (pin "55") (pinfunction "BCBUS4/TXLED#/GPIOH4_55") (pintype "bidirectional"))
      (node (ref "U6") (pin "M3") (pinfunction "1_M3") (pintype "bidirectional"))
    )
    (net (code "83") (name "FTDI_TXE") (class "Default")
      (node (ref "U2") (pin "52") (pinfunction "BCBUS1/GPIOH2_52") (pintype "bidirectional"))
      (node (ref "U6") (pin "N1") (pinfunction "1_N1") (pintype "bidirectional"))
    )
    (net (code "84") (name "FTDI_WR") (class "Default")
      (node (ref "U2") (pin "54") (pinfunction "BCBUS3/RXLED#/GPIOH3_54") (pintype "bidirectional"))
      (node (ref "U6") (pin "M2") (pinfunction "1_M2") (pintype "bidirectional"))
    )
    (net (code "85") (name "GND") (class "Default")
      (node (ref "C1") (pin "2") (pinfunction "2_2") (pintype "passive"))
      (node (ref "C10") (pin "2") (pinfunction "2_2") (pintype "passive"))
      (node (ref "C11") (pin "2") (pinfunction "2_2") (pintype "passive"))
      (node (ref "C12") (pin "2") (pinfunction "2_2") (pintype "passive"))
      (node (ref "C13") (pin "2") (pinfunction "2_2") (pintype "passive"))
      (node (ref "C14") (pin "2") (pinfunction "2_2") (pintype "passive"))
      (node (ref "C15") (pin "2") (pinfunction "2_2") (pintype "passive"))
      (node (ref "C16") (pin "2") (pinfunction "2_2") (pintype "passive"))
      (node (ref "C17") (pin "2") (pinfunction "2_2") (pintype "passive"))
      (node (ref "C18") (pin "2") (pinfunction "2_2") (pintype "passive"))
      (node (ref "C19") (pin "2") (pinfunction "2_2") (pintype "passive"))
      (node (ref "C2") (pin "2") (pinfunction "2_2") (pintype "passive"))
      (node (ref "C20") (pin "2") (pinfunction "2_2") (pintype "passive"))
      (node (ref "C21") (pin "2") (pinfunction "2_2") (pintype "passive"))
      (node (ref "C22") (pin "2") (pinfunction "2_2") (pintype "passive"))
      (node (ref "C23") (pin "2") (pinfunction "2_2") (pintype "passive"))
      (node (ref "C24") (pin "2") (pinfunction "2_2") (pintype "passive"))
      (node (ref "C25") (pin "2") (pinfunction "2_2") (pintype "passive"))
      (node (ref "C26") (pin "2") (pinfunction "2_2") (pintype "passive"))
      (node (ref "C27") (pin "2") (pinfunction "2_2") (pintype "passive"))
      (node (ref "C28") (pin "2") (pinfunction "2_2") (pintype "passive"))
      (node (ref "C29") (pin "2") (pinfunction "2_2") (pintype "passive"))
      (node (ref "C3") (pin "2") (pinfunction "2_2") (pintype "passive"))
      (node (ref "C30") (pin "2") (pinfunction "2_2") (pintype "passive"))
      (node (ref "C31") (pin "2") (pinfunction "2_2") (pintype "passive"))
      (node (ref "C32") (pin "2") (pinfunction "2_2") (pintype "passive"))
      (node (ref "C33") (pin "2") (pinfunction "2_2") (pintype "passive"))
      (node (ref "C34") (pin "2") (pinfunction "2_2") (pintype "passive"))
      (node (ref "C35") (pin "2") (pinfunction "2_2") (pintype "passive"))
      (node (ref "C36") (pin "2") (pinfunction "2_2") (pintype "passive"))
      (node (ref "C37") (pin "2") (pinfunction "2_2") (pintype "passive"))
      (node (ref "C38") (pin "2") (pinfunction "2_2") (pintype "passive"))
      (node (ref "C39") (pin "2") (pinfunction "2_2") (pintype "passive"))
      (node (ref "C4") (pin "2") (pinfunction "2_2") (pintype "passive"))
      (node (ref "C40") (pin "2") (pinfunction "2_2") (pintype "passive"))
      (node (ref "C5") (pin "2") (pinfunction "2_2") (pintype "passive"))
      (node (ref "C6") (pin "2") (pinfunction "2_2") (pintype "passive"))
      (node (ref "C7") (pin "2") (pinfunction "2_2") (pintype "passive"))
      (node (ref "C8") (pin "2") (pinfunction "2_2") (pintype "passive"))
      (node (ref "C9") (pin "2") (pinfunction "2_2") (pintype "passive"))
      (node (ref "J2") (pin "11") (pinfunction "CLOCKSHIELD_11") (pintype "bidirectional"))
      (node (ref "J2") (pin "14") (pinfunction "RES_14") (pintype "bidirectional"))
      (node (ref "J2") (pin "17") (pinfunction "DDC/CEC-GRND_17") (pintype "bidirectional"))
      (node (ref "J2") (pin "2") (pinfunction "DATA2SHIELD_2") (pintype "bidirectional"))
      (node (ref "J2") (pin "5") (pinfunction "DATA1SHIELD_5") (pintype "bidirectional"))
      (node (ref "J2") (pin "8") (pinfunction "DATA0SHIELD_8") (pintype "bidirectional"))
      (node (ref "J3") (pin "11") (pinfunction "CLOCKSHIELD_11") (pintype "bidirectional"))
      (node (ref "J3") (pin "14") (pinfunction "RES_14") (pintype "bidirectional"))
      (node (ref "J3") (pin "17") (pinfunction "DDC/CEC-GRND_17") (pintype "bidirectional"))
      (node (ref "J3") (pin "2") (pinfunction "DATA2SHIELD_2") (pintype "bidirectional"))
      (node (ref "J3") (pin "5") (pinfunction "DATA1SHIELD_5") (pintype "bidirectional"))
      (node (ref "J3") (pin "8") (pinfunction "DATA0SHIELD_8") (pintype "bidirectional"))
      (node (ref "J4") (pin "P$1") (pinfunction "P1_P$1") (pintype "bidirectional"))
      (node (ref "J4") (pin "P$17") (pinfunction "P17_P$17") (pintype "bidirectional"))
      (node (ref "J4") (pin "P$6") (pinfunction "P6_P$6") (pintype "bidirectional"))
      (node (ref "J4") (pin "P$9") (pinfunction "P9_P$9") (pintype "bidirectional"))
      (node (ref "J5") (pin "G1") (pinfunction "GND0_G1") (pintype "bidirectional"))
      (node (ref "J5") (pin "G2") (pinfunction "GND1_G2") (pintype "bidirectional"))
      (node (ref "J5") (pin "G3") (pinfunction "GND2_G3") (pintype "bidirectional"))
      (node (ref "J5") (pin "G4") (pinfunction "GND3_G4") (pintype "bidirectional"))
      (node (ref "J5") (pin "T6") (pinfunction "VSS_T6") (pintype "bidirectional"))
      (node (ref "J6") (pin "P$1") (pinfunction "P1_P$1") (pintype "bidirectional"))
      (node (ref "J6") (pin "P$13") (pinfunction "P13_P$13") (pintype "bidirectional"))
      (node (ref "J6") (pin "P$21") (pinfunction "P21_P$21") (pintype "bidirectional"))
      (node (ref "J6") (pin "P$6") (pinfunction "P6_P$6") (pintype "bidirectional"))
      (node (ref "JP5") (pin "EARTH") (pinfunction "EARTH_EARTH") (pintype "bidirectional"))
      (node (ref "R1") (pin "1") (pinfunction "1_1") (pintype "passive"))
      (node (ref "R15") (pin "1") (pinfunction "1_1") (pintype "passive"))
      (node (ref "R17") (pin "1") (pinfunction "1_1") (pintype "passive"))
      (node (ref "R2") (pin "1") (pinfunction "1_1") (pintype "passive"))
      (node (ref "R21") (pin "1") (pinfunction "1_1") (pintype "passive"))
      (node (ref "R3") (pin "1") (pinfunction "1_1") (pintype "passive"))
      (node (ref "R4") (pin "1") (pinfunction "1_1") (pintype "passive"))
      (node (ref "R5") (pin "1") (pinfunction "1_1") (pintype "passive"))
      (node (ref "RN1") (pin "1") (pinfunction "1_1") (pintype "passive"))
      (node (ref "RN1") (pin "2") (pinfunction "1_2") (pintype "passive"))
      (node (ref "RN1") (pin "3") (pinfunction "1_3") (pintype "passive"))
      (node (ref "RN1") (pin "4") (pinfunction "1_4") (pintype "passive"))
      (node (ref "RN2") (pin "1") (pinfunction "1_1") (pintype "passive"))
      (node (ref "RN2") (pin "2") (pinfunction "1_2") (pintype "passive"))
      (node (ref "RN2") (pin "3") (pinfunction "1_3") (pintype "passive"))
      (node (ref "RN2") (pin "4") (pinfunction "1_4") (pintype "passive"))
      (node (ref "S1") (pin "1") (pinfunction "1_1") (pintype "passive"))
      (node (ref "S1") (pin "2") (pinfunction "2_2") (pintype "passive"))
      (node (ref "S2") (pin "1") (pinfunction "1_1") (pintype "passive"))
      (node (ref "S2") (pin "2") (pinfunction "2_2") (pintype "passive"))
      (node (ref "S2") (pin "3") (pinfunction "3_3") (pintype "passive"))
      (node (ref "S2") (pin "4") (pinfunction "4_4") (pintype "passive"))
      (node (ref "U$7") (pin "P$12") (pinfunction "P12_P$12") (pintype "bidirectional"))
      (node (ref "U$7") (pin "P$20") (pinfunction "P20_P$20") (pintype "bidirectional"))
      (node (ref "U$7") (pin "P$4") (pinfunction "P4_P$4") (pintype "bidirectional"))
      (node (ref "U$8") (pin "P$16") (pinfunction "P16_P$16") (pintype "bidirectional"))
      (node (ref "U$8") (pin "P$24") (pinfunction "P24_P$24") (pintype "bidirectional"))
      (node (ref "U$8") (pin "P$8") (pinfunction "P8_P$8") (pintype "bidirectional"))
      (node (ref "U1") (pin "2") (pinfunction "GND_2") (pintype "power_in"))
      (node (ref "U10") (pin "4") (pinfunction "1_4") (pintype "input"))
      (node (ref "U11") (pin "1") (pinfunction "GND_1") (pintype "bidirectional"))
      (node (ref "U2") (pin "1") (pinfunction "GND0_1") (pintype "bidirectional"))
      (node (ref "U2") (pin "10") (pinfunction "AGND_10") (pintype "bidirectional"))
      (node (ref "U2") (pin "11") (pinfunction "GND2_11") (pintype "bidirectional"))
      (node (ref "U2") (pin "13") (pinfunction "TEST_13") (pintype "bidirectional"))
      (node (ref "U2") (pin "15") (pinfunction "GND3_15") (pintype "bidirectional"))
      (node (ref "U2") (pin "25") (pinfunction "GND4_25") (pintype "bidirectional"))
      (node (ref "U2") (pin "35") (pinfunction "GND5_35") (pintype "bidirectional"))
      (node (ref "U2") (pin "47") (pinfunction "GND6_47") (pintype "bidirectional"))
      (node (ref "U2") (pin "5") (pinfunction "GND1_5") (pintype "bidirectional"))
      (node (ref "U2") (pin "51") (pinfunction "GND7_51") (pintype "bidirectional"))
      (node (ref "U3") (pin "12") (pinfunction "DGND_12") (pintype "power_in"))
      (node (ref "U3") (pin "3") (pinfunction "AGND_3") (pintype "power_in"))
      (node (ref "U4") (pin "1") (pinfunction "GND_1") (pintype "input"))
      (node (ref "U5") (pin "1") (pinfunction "GND_1") (pintype "input"))
      (node (ref "U6") (pin "A1") (pinfunction "1_A1") (pintype "input"))
      (node (ref "U6") (pin "A16") (pinfunction "1_A16") (pintype "input"))
      (node (ref "U6") (pin "B11") (pinfunction "1_B11") (pintype "input"))
      (node (ref "U6") (pin "B7") (pinfunction "1_B7") (pintype "input"))
      (node (ref "U6") (pin "C4") (pinfunction "1_C4") (pintype "bidirectional"))
      (node (ref "U6") (pin "D13") (pinfunction "1_D13") (pintype "input"))
      (node (ref "U6") (pin "D4") (pinfunction "1_D4") (pintype "input"))
      (node (ref "U6") (pin "E9") (pinfunction "1_E9") (pintype "input"))
      (node (ref "U6") (pin "G15") (pinfunction "1_G15") (pintype "input"))
      (node (ref "U6") (pin "G2") (pinfunction "1_G2") (pintype "input"))
      (node (ref "U6") (pin "G8") (pinfunction "1_G8") (pintype "input"))
      (node (ref "U6") (pin "H12") (pinfunction "1_H12") (pintype "input"))
      (node (ref "U6") (pin "H7") (pinfunction "1_H7") (pintype "input"))
      (node (ref "U6") (pin "H9") (pinfunction "1_H9") (pintype "input"))
      (node (ref "U6") (pin "J5") (pinfunction "1_J5") (pintype "input"))
      (node (ref "U6") (pin "J8") (pinfunction "1_J8") (pintype "input"))
      (node (ref "U6") (pin "K7") (pinfunction "1_K7") (pintype "input"))
      (node (ref "U6") (pin "K9") (pinfunction "1_K9") (pintype "input"))
      (node (ref "U6") (pin "L15") (pinfunction "1_L15") (pintype "input"))
      (node (ref "U6") (pin "L2") (pinfunction "1_L2") (pintype "input"))
      (node (ref "U6") (pin "M8") (pinfunction "1_M8") (pintype "input"))
      (node (ref "U6") (pin "N11") (pinfunction "1_N11") (pintype "bidirectional"))
      (node (ref "U6") (pin "N13") (pinfunction "1_N13") (pintype "input"))
      (node (ref "U6") (pin "P14") (pinfunction "1_P14") (pintype "input"))
      (node (ref "U6") (pin "P3") (pinfunction "1_P3") (pintype "input"))
      (node (ref "U6") (pin "R10") (pinfunction "1_R10") (pintype "input"))
      (node (ref "U6") (pin "R6") (pinfunction "1_R6") (pintype "input"))
      (node (ref "U6") (pin "T1") (pinfunction "1_T1") (pintype "input"))
      (node (ref "U6") (pin "T16") (pinfunction "1_T16") (pintype "input"))
      (node (ref "U7") (pin "2") (pinfunction "GND_2") (pintype "bidirectional"))
      (node (ref "U8") (pin "2") (pinfunction "GND_2") (pintype "bidirectional"))
      (node (ref "U9") (pin "12") (pinfunction "P$1_12") (pintype "bidirectional"))
      (node (ref "U9") (pin "28") (pinfunction "P$1_28") (pintype "bidirectional"))
      (node (ref "U9") (pin "41") (pinfunction "P$1_41") (pintype "bidirectional"))
      (node (ref "U9") (pin "46") (pinfunction "P$1_46") (pintype "bidirectional"))
      (node (ref "U9") (pin "52") (pinfunction "P$1_52") (pintype "bidirectional"))
      (node (ref "U9") (pin "54") (pinfunction "P$1_54") (pintype "bidirectional"))
      (node (ref "U9") (pin "6") (pinfunction "P$1_6") (pintype "bidirectional"))
      (node (ref "X1") (pin "5") (pinfunction "5_5") (pintype "input"))
    )
    (net (code "86") (name "LDQM") (class "Default")
      (node (ref "U6") (pin "T5") (pinfunction "1_T5") (pintype "bidirectional"))
      (node (ref "U9") (pin "15") (pinfunction "P$1_15") (pintype "bidirectional"))
    )
    (net (code "87") (name "LED1") (class "Default")
      (node (ref "LED1") (pin "A") (pinfunction "A_A") (pintype "passive"))
      (node (ref "U6") (pin "P11") (pinfunction "1_P11") (pintype "bidirectional"))
    )
    (net (code "88") (name "LED2") (class "Default")
      (node (ref "LED2") (pin "A") (pinfunction "A_A") (pintype "passive"))
      (node (ref "U6") (pin "N9") (pinfunction "1_N9") (pintype "bidirectional"))
    )
    (net (code "89") (name "LED3") (class "Default")
      (node (ref "LED3") (pin "A") (pinfunction "A_A") (pintype "passive"))
      (node (ref "U6") (pin "P9") (pinfunction "1_P9") (pintype "bidirectional"))
    )
    (net (code "90") (name "LED4") (class "Default")
      (node (ref "LED4") (pin "A") (pinfunction "A_A") (pintype "passive"))
      (node (ref "U6") (pin "M9") (pinfunction "1_M9") (pintype "bidirectional"))
    )
    (net (code "91") (name "LED5") (class "Default")
      (node (ref "LED5") (pin "A") (pinfunction "A_A") (pintype "passive"))
      (node (ref "U6") (pin "N8") (pinfunction "1_N8") (pintype "bidirectional"))
    )
    (net (code "92") (name "LED6") (class "Default")
      (node (ref "LED6") (pin "A") (pinfunction "A_A") (pintype "passive"))
      (node (ref "U6") (pin "P7") (pinfunction "1_P7") (pintype "bidirectional"))
    )
    (net (code "93") (name "LED7") (class "Default")
      (node (ref "LED7") (pin "A") (pinfunction "A_A") (pintype "passive"))
      (node (ref "U6") (pin "P8") (pinfunction "1_P8") (pintype "bidirectional"))
    )
    (net (code "94") (name "LED8") (class "Default")
      (node (ref "LED8") (pin "A") (pinfunction "A_A") (pintype "passive"))
      (node (ref "U6") (pin "T8") (pinfunction "1_T8") (pintype "bidirectional"))
    )
    (net (code "95") (name "Net-(C14-Pad1)") (class "Default")
      (node (ref "C14") (pin "1") (pinfunction "1_1") (pintype "passive"))
      (node (ref "JP5") (pin "TIP") (pinfunction "TIP_TIP") (pintype "bidirectional"))
      (node (ref "R20") (pin "2") (pinfunction "2_2") (pintype "passive"))
    )
    (net (code "96") (name "Net-(C15-Pad1)") (class "Default")
      (node (ref "C15") (pin "1") (pinfunction "1_1") (pintype "passive"))
      (node (ref "JP5") (pin "RING1") (pinfunction "RING1_RING1") (pintype "bidirectional"))
      (node (ref "R19") (pin "2") (pinfunction "2_2") (pintype "passive"))
    )
    (net (code "97") (name "Net-(C37-Pad1)") (class "Default")
      (node (ref "C37") (pin "1") (pinfunction "1_1") (pintype "passive"))
      (node (ref "R1") (pin "2") (pinfunction "2_2") (pintype "passive"))
      (node (ref "X1") (pin "M1") (pinfunction "M1_M1") (pintype "bidirectional"))
      (node (ref "X1") (pin "M2") (pinfunction "M2_M2") (pintype "bidirectional"))
      (node (ref "X1") (pin "M3") (pinfunction "M3_M3") (pintype "bidirectional"))
      (node (ref "X1") (pin "M4") (pinfunction "M4_M4") (pintype "bidirectional"))
    )
    (net (code "98") (name "Net-(C39-Pad1)") (class "Default")
      (node (ref "C39") (pin "1") (pinfunction "1_1") (pintype "passive"))
      (node (ref "J2") (pin "SH1") (pinfunction "SH1_SH1") (pintype "bidirectional"))
      (node (ref "J2") (pin "SH2") (pinfunction "SH2_SH2") (pintype "bidirectional"))
      (node (ref "J2") (pin "SH3") (pinfunction "SH3_SH3") (pintype "bidirectional"))
      (node (ref "J2") (pin "SH4") (pinfunction "SH4_SH4") (pintype "bidirectional"))
      (node (ref "R2") (pin "2") (pinfunction "2_2") (pintype "passive"))
    )
    (net (code "99") (name "Net-(C40-Pad1)") (class "Default")
      (node (ref "C40") (pin "1") (pinfunction "1_1") (pintype "passive"))
      (node (ref "J3") (pin "SH1") (pinfunction "SH1_SH1") (pintype "bidirectional"))
      (node (ref "J3") (pin "SH2") (pinfunction "SH2_SH2") (pintype "bidirectional"))
      (node (ref "J3") (pin "SH3") (pinfunction "SH3_SH3") (pintype "bidirectional"))
      (node (ref "J3") (pin "SH4") (pinfunction "SH4_SH4") (pintype "bidirectional"))
      (node (ref "R3") (pin "2") (pinfunction "2_2") (pintype "passive"))
    )
    (net (code "100") (name "Net-(J2-DETECT)") (class "Default")
      (node (ref "J2") (pin "19") (pinfunction "DETECT_19") (pintype "bidirectional"))
      (node (ref "R14") (pin "2") (pinfunction "2_2") (pintype "passive"))
    )
    (net (code "101") (name "Net-(J2-SCL)") (class "Default")
      (node (ref "J2") (pin "15") (pinfunction "SCL_15") (pintype "bidirectional"))
      (node (ref "RN5") (pin "6") (pinfunction "2_6") (pintype "passive"))
      (node (ref "U11") (pin "6") (pinfunction "SCL2_6") (pintype "bidirectional"))
    )
    (net (code "102") (name "Net-(J2-SDA)") (class "Default")
      (node (ref "J2") (pin "16") (pinfunction "SDA_16") (pintype "bidirectional"))
      (node (ref "RN5") (pin "5") (pinfunction "2_5") (pintype "passive"))
      (node (ref "U11") (pin "5") (pinfunction "SDA2_5") (pintype "bidirectional"))
    )
    (net (code "103") (name "Net-(J3-DETECT)") (class "Default")
      (node (ref "J3") (pin "19") (pinfunction "DETECT_19") (pintype "bidirectional"))
      (node (ref "R17") (pin "2") (pinfunction "2_2") (pintype "passive"))
    )
    (net (code "104") (name "Net-(LED9-PadC)") (class "Default")
      (node (ref "LED9") (pin "C") (pinfunction "C_C") (pintype "passive"))
      (node (ref "R21") (pin "2") (pinfunction "2_2") (pintype "passive"))
    )
    (net (code "105") (name "Net-(Q1-2)") (class "Default")
      (node (ref "C10") (pin "1") (pinfunction "1_1") (pintype "passive"))
      (node (ref "Q1") (pin "3") (pinfunction "2_3") (pintype "passive"))
      (node (ref "U2") (pin "3") (pinfunction "OSC0_3") (pintype "bidirectional"))
    )
    (net (code "106") (name "Net-(RN1A-2)") (class "Default")
      (node (ref "LED4") (pin "C") (pinfunction "C_C") (pintype "passive"))
      (node (ref "RN1") (pin "8") (pinfunction "2_8") (pintype "passive"))
    )
    (net (code "107") (name "Net-(RN1B-2)") (class "Default")
      (node (ref "LED3") (pin "C") (pinfunction "C_C") (pintype "passive"))
      (node (ref "RN1") (pin "7") (pinfunction "2_7") (pintype "passive"))
    )
    (net (code "108") (name "Net-(RN1C-2)") (class "Default")
      (node (ref "LED2") (pin "C") (pinfunction "C_C") (pintype "passive"))
      (node (ref "RN1") (pin "6") (pinfunction "2_6") (pintype "passive"))
    )
    (net (code "109") (name "Net-(RN1D-2)") (class "Default")
      (node (ref "LED1") (pin "C") (pinfunction "C_C") (pintype "passive"))
      (node (ref "RN1") (pin "5") (pinfunction "2_5") (pintype "passive"))
    )
    (net (code "110") (name "Net-(RN2A-2)") (class "Default")
      (node (ref "LED6") (pin "C") (pinfunction "C_C") (pintype "passive"))
      (node (ref "RN2") (pin "8") (pinfunction "2_8") (pintype "passive"))
    )
    (net (code "111") (name "Net-(RN2B-2)") (class "Default")
      (node (ref "LED7") (pin "C") (pinfunction "C_C") (pintype "passive"))
      (node (ref "RN2") (pin "7") (pinfunction "2_7") (pintype "passive"))
    )
    (net (code "112") (name "Net-(RN2C-2)") (class "Default")
      (node (ref "LED5") (pin "C") (pinfunction "C_C") (pintype "passive"))
      (node (ref "RN2") (pin "6") (pinfunction "2_6") (pintype "passive"))
    )
    (net (code "113") (name "Net-(RN2D-2)") (class "Default")
      (node (ref "LED8") (pin "C") (pinfunction "C_C") (pintype "passive"))
      (node (ref "RN2") (pin "5") (pinfunction "2_5") (pintype "passive"))
    )
    (net (code "114") (name "Net-(RN3B-2)") (class "Default")
      (node (ref "R7") (pin "2") (pinfunction "2_2") (pintype "passive"))
      (node (ref "RN3") (pin "1") (pinfunction "1_1") (pintype "passive"))
      (node (ref "RN3") (pin "3") (pinfunction "2_3") (pintype "passive"))
      (node (ref "RN4") (pin "1") (pinfunction "1_1") (pintype "passive"))
      (node (ref "RN4") (pin "3") (pinfunction "2_3") (pintype "passive"))
      (node (ref "RN8") (pin "1") (pinfunction "1_1") (pintype "passive"))
      (node (ref "RN8") (pin "3") (pinfunction "2_3") (pintype "passive"))
      (node (ref "RN9") (pin "1") (pinfunction "1_1") (pintype "passive"))
      (node (ref "RN9") (pin "3") (pinfunction "2_3") (pintype "passive"))
    )
    (net (code "115") (name "Net-(U1-DO)") (class "Default")
      (node (ref "R11") (pin "1") (pinfunction "1_1") (pintype "passive"))
      (node (ref "R8") (pin "1") (pinfunction "1_1") (pintype "passive"))
      (node (ref "U1") (pin "1") (pinfunction "DO_1") (pintype "output"))
    )
    (net (code "116") (name "Net-(U2-DM)") (class "Default")
      (node (ref "U2") (pin "7") (pinfunction "DM_7") (pintype "bidirectional"))
      (node (ref "X1") (pin "2") (pinfunction "2_2") (pintype "input"))
    )
    (net (code "117") (name "Net-(U2-DP)") (class "Default")
      (node (ref "U2") (pin "8") (pinfunction "DP_8") (pintype "bidirectional"))
      (node (ref "X1") (pin "3") (pinfunction "3_3") (pintype "input"))
    )
    (net (code "118") (name "Net-(U2-OSCI)") (class "Default")
      (node (ref "C5") (pin "1") (pinfunction "1_1") (pintype "passive"))
      (node (ref "Q1") (pin "1") (pinfunction "1_1") (pintype "passive"))
      (node (ref "U2") (pin "2") (pinfunction "OSCI_2") (pintype "bidirectional"))
    )
    (net (code "119") (name "Net-(U2-REF)") (class "Default")
      (node (ref "R15") (pin "2") (pinfunction "2_2") (pintype "passive"))
      (node (ref "U2") (pin "6") (pinfunction "REF_6") (pintype "bidirectional"))
    )
    (net (code "120") (name "Net-(U2-RESET#)") (class "Default")
      (node (ref "R16") (pin "2") (pinfunction "2_2") (pintype "passive"))
      (node (ref "U2") (pin "14") (pinfunction "RESET#_14") (pintype "bidirectional"))
    )
    (net (code "121") (name "Net-(U2-VPHY)") (class "Default")
      (node (ref "C1") (pin "1") (pinfunction "1_1") (pintype "passive"))
      (node (ref "C3") (pin "1") (pinfunction "1_1") (pintype "passive"))
      (node (ref "L1") (pin "1") (pinfunction "1_1") (pintype "passive"))
      (node (ref "U2") (pin "4") (pinfunction "VPHY_4") (pintype "bidirectional"))
    )
    (net (code "122") (name "Net-(U2-VPLL)") (class "Default")
      (node (ref "C6") (pin "1") (pinfunction "1_1") (pintype "passive"))
      (node (ref "C8") (pin "1") (pinfunction "1_1") (pintype "passive"))
      (node (ref "L2") (pin "1") (pinfunction "1_1") (pintype "passive"))
      (node (ref "U2") (pin "9") (pinfunction "VPLL_9") (pintype "bidirectional"))
    )
    (net (code "123") (name "Net-(U3-VA)") (class "Default")
      (node (ref "C11") (pin "1") (pinfunction "1_1") (pintype "passive"))
      (node (ref "L3") (pin "1") (pinfunction "1_1") (pintype "passive"))
      (node (ref "U3") (pin "2") (pinfunction "VA_2") (pintype "power_in"))
    )
    (net (code "124") (name "Net-(U11-EN)") (class "Default")
      (node (ref "C33") (pin "1") (pinfunction "1_1") (pintype "passive"))
      (node (ref "R6") (pin "2") (pinfunction "2_2") (pintype "passive"))
      (node (ref "U11") (pin "7") (pinfunction "VREF2_7") (pintype "bidirectional"))
      (node (ref "U11") (pin "8") (pinfunction "EN_8") (pintype "bidirectional"))
    )
    (net (code "125") (name "PORTA0") (class "Default")
      (node (ref "U$7") (pin "P$1") (pinfunction "P1_P$1") (pintype "bidirectional"))
      (node (ref "U6") (pin "E7") (pinfunction "1_E7") (pintype "bidirectional"))
    )
    (net (code "126") (name "PORTA1") (class "Default")
      (node (ref "U$8") (pin "P$1") (pinfunction "P1_P$1") (pintype "bidirectional"))
      (node (ref "U6") (pin "C8") (pinfunction "1_C8") (pintype "bidirectional"))
    )
    (net (code "127") (name "PORTA2") (class "Default")
      (node (ref "U$7") (pin "P$2") (pinfunction "P2_P$2") (pintype "bidirectional"))
      (node (ref "U6") (pin "D8") (pinfunction "1_D8") (pintype "bidirectional"))
    )
    (net (code "128") (name "PORTA3") (class "Default")
      (node (ref "U$8") (pin "P$2") (pinfunction "P2_P$2") (pintype "bidirectional"))
      (node (ref "U6") (pin "E8") (pinfunction "1_E8") (pintype "bidirectional"))
    )
    (net (code "129") (name "PORTA4") (class "Default")
      (node (ref "U$7") (pin "P$3") (pinfunction "P3_P$3") (pintype "bidirectional"))
      (node (ref "U6") (pin "D9") (pinfunction "1_D9") (pintype "bidirectional"))
    )
    (net (code "130") (name "PORTA5") (class "Default")
      (node (ref "U$8") (pin "P$3") (pinfunction "P3_P$3") (pintype "bidirectional"))
      (node (ref "U6") (pin "A10") (pinfunction "1_A10") (pintype "bidirectional"))
    )
    (net (code "131") (name "PORTA6") (class "Default")
      (node (ref "U$7") (pin "P$5") (pinfunction "P5_P$5") (pintype "bidirectional"))
      (node (ref "U6") (pin "B10") (pinfunction "1_B10") (pintype "bidirectional"))
    )
    (net (code "132") (name "PORTA7") (class "Default")
      (node (ref "U$8") (pin "P$5") (pinfunction "P5_P$5") (pintype "bidirectional"))
      (node (ref "U6") (pin "C10") (pinfunction "1_C10") (pintype "bidirectional"))
    )
    (net (code "133") (name "PORTA8") (class "Default")
      (node (ref "U$7") (pin "P$6") (pinfunction "P6_P$6") (pintype "bidirectional"))
      (node (ref "U6") (pin "E10") (pinfunction "1_E10") (pintype "bidirectional"))
    )
    (net (code "134") (name "PORTA9") (class "Default")
      (node (ref "U$8") (pin "P$6") (pinfunction "P6_P$6") (pintype "bidirectional"))
      (node (ref "U6") (pin "F9") (pinfunction "1_F9") (pintype "bidirectional"))
    )
    (net (code "135") (name "PORTA10") (class "Default")
      (node (ref "U$7") (pin "P$7") (pinfunction "P7_P$7") (pintype "bidirectional"))
      (node (ref "U6") (pin "F10") (pinfunction "1_F10") (pintype "bidirectional"))
    )
    (net (code "136") (name "PORTA11") (class "Default")
      (node (ref "U$8") (pin "P$7") (pinfunction "P7_P$7") (pintype "bidirectional"))
      (node (ref "U6") (pin "D11") (pinfunction "1_D11") (pintype "bidirectional"))
    )
    (net (code "137") (name "PORTB0") (class "Default")
      (node (ref "U$7") (pin "P$9") (pinfunction "P9_P$9") (pintype "bidirectional"))
      (node (ref "U6") (pin "E11") (pinfunction "1_E11") (pintype "bidirectional"))
    )
    (net (code "138") (name "PORTB1") (class "Default")
      (node (ref "U$8") (pin "P$9") (pinfunction "P9_P$9") (pintype "bidirectional"))
      (node (ref "U6") (pin "D14") (pinfunction "1_D14") (pintype "bidirectional"))
    )
    (net (code "139") (name "PORTB2") (class "Default")
      (node (ref "U$7") (pin "P$10") (pinfunction "P10_P$10") (pintype "bidirectional"))
      (node (ref "U6") (pin "D12") (pinfunction "1_D12") (pintype "bidirectional"))
    )
    (net (code "140") (name "PORTB3") (class "Default")
      (node (ref "U$8") (pin "P$10") (pinfunction "P10_P$10") (pintype "bidirectional"))
      (node (ref "U6") (pin "E12") (pinfunction "1_E12") (pintype "bidirectional"))
    )
    (net (code "141") (name "PORTB4") (class "Default")
      (node (ref "U$7") (pin "P$11") (pinfunction "P11_P$11") (pintype "bidirectional"))
      (node (ref "U6") (pin "E13") (pinfunction "1_E13") (pintype "bidirectional"))
    )
    (net (code "142") (name "PORTB5") (class "Default")
      (node (ref "U$8") (pin "P$11") (pinfunction "P11_P$11") (pintype "bidirectional"))
      (node (ref "U6") (pin "F13") (pinfunction "1_F13") (pintype "bidirectional"))
    )
    (net (code "143") (name "PORTB6") (class "Default")
      (node (ref "U$7") (pin "P$13") (pinfunction "P13_P$13") (pintype "bidirectional"))
      (node (ref "U6") (pin "F12") (pinfunction "1_F12") (pintype "bidirectional"))
    )
    (net (code "144") (name "PORTB7") (class "Default")
      (node (ref "U$8") (pin "P$13") (pinfunction "P13_P$13") (pintype "bidirectional"))
      (node (ref "U6") (pin "F14") (pinfunction "1_F14") (pintype "bidirectional"))
    )
    (net (code "145") (name "PORTB8") (class "Default")
      (node (ref "U$7") (pin "P$14") (pinfunction "P14_P$14") (pintype "bidirectional"))
      (node (ref "U6") (pin "G12") (pinfunction "1_G12") (pintype "bidirectional"))
    )
    (net (code "146") (name "PORTB9") (class "Default")
      (node (ref "U$8") (pin "P$14") (pinfunction "P14_P$14") (pintype "bidirectional"))
      (node (ref "U6") (pin "G14") (pinfunction "1_G14") (pintype "bidirectional"))
    )
    (net (code "147") (name "PORTB10") (class "Default")
      (node (ref "U$7") (pin "P$15") (pinfunction "P15_P$15") (pintype "bidirectional"))
      (node (ref "U6") (pin "H14") (pinfunction "1_H14") (pintype "bidirectional"))
    )
    (net (code "148") (name "PORTB11") (class "Default")
      (node (ref "U$8") (pin "P$15") (pinfunction "P15_P$15") (pintype "bidirectional"))
      (node (ref "U6") (pin "J14") (pinfunction "1_J14") (pintype "bidirectional"))
    )
    (net (code "149") (name "PORTC0") (class "Default")
      (node (ref "U$7") (pin "P$17") (pinfunction "P17_P$17") (pintype "bidirectional"))
      (node (ref "U6") (pin "J13") (pinfunction "1_J13") (pintype "bidirectional"))
    )
    (net (code "150") (name "PORTC1") (class "Default")
      (node (ref "U$8") (pin "P$17") (pinfunction "P17_P$17") (pintype "bidirectional"))
      (node (ref "U6") (pin "J12") (pinfunction "1_J12") (pintype "bidirectional"))
    )
    (net (code "151") (name "PORTC2") (class "Default")
      (node (ref "U$7") (pin "P$18") (pinfunction "P18_P$18") (pintype "bidirectional"))
      (node (ref "U6") (pin "K14") (pinfunction "1_K14") (pintype "bidirectional"))
    )
    (net (code "152") (name "PORTC3") (class "Default")
      (node (ref "U$8") (pin "P$18") (pinfunction "P18_P$18") (pintype "bidirectional"))
      (node (ref "U6") (pin "L14") (pinfunction "1_L14") (pintype "bidirectional"))
    )
    (net (code "153") (name "PORTC4") (class "Default")
      (node (ref "U$7") (pin "P$19") (pinfunction "P19_P$19") (pintype "bidirectional"))
      (node (ref "U6") (pin "L13") (pinfunction "1_L13") (pintype "bidirectional"))
    )
    (net (code "154") (name "PORTC5") (class "Default")
      (node (ref "U$8") (pin "P$19") (pinfunction "P19_P$19") (pintype "bidirectional"))
      (node (ref "U6") (pin "M14") (pinfunction "1_M14") (pintype "bidirectional"))
    )
    (net (code "155") (name "PORTC6") (class "Default")
      (node (ref "U$7") (pin "P$21") (pinfunction "P21_P$21") (pintype "bidirectional"))
      (node (ref "U6") (pin "M13") (pinfunction "1_M13") (pintype "bidirectional"))
    )
    (net (code "156") (name "PORTC7") (class "Default")
      (node (ref "U$8") (pin "P$21") (pinfunction "P21_P$21") (pintype "bidirectional"))
      (node (ref "U6") (pin "N14") (pinfunction "1_N14") (pintype "bidirectional"))
    )
    (net (code "157") (name "PORTC8") (class "Default")
      (node (ref "U$7") (pin "P$22") (pinfunction "P22_P$22") (pintype "bidirectional"))
      (node (ref "U6") (pin "M12") (pinfunction "1_M12") (pintype "bidirectional"))
    )
    (net (code "158") (name "PORTC9") (class "Default")
      (node (ref "U$8") (pin "P$22") (pinfunction "P22_P$22") (pintype "bidirectional"))
      (node (ref "U6") (pin "N12") (pinfunction "1_N12") (pintype "bidirectional"))
    )
    (net (code "159") (name "PORTC10") (class "Default")
      (node (ref "U$7") (pin "P$23") (pinfunction "P23_P$23") (pintype "bidirectional"))
      (node (ref "U6") (pin "P12") (pinfunction "1_P12") (pintype "bidirectional"))
    )
    (net (code "160") (name "PORTC11") (class "Default")
      (node (ref "U$8") (pin "P$23") (pinfunction "P23_P$23") (pintype "bidirectional"))
      (node (ref "U6") (pin "M11") (pinfunction "1_M11") (pintype "bidirectional"))
    )
    (net (code "161") (name "PORTD0") (class "Default")
      (node (ref "J4") (pin "P$7") (pinfunction "P7_P$7") (pintype "bidirectional"))
      (node (ref "U6") (pin "D6") (pinfunction "1_D6") (pintype "bidirectional"))
    )
    (net (code "162") (name "PORTD1") (class "Default")
      (node (ref "J6") (pin "P$7") (pinfunction "P7_P$7") (pintype "bidirectional"))
      (node (ref "U6") (pin "C6") (pinfunction "1_C6") (pintype "bidirectional"))
    )
    (net (code "163") (name "PORTD2") (class "Default")
      (node (ref "J4") (pin "P$8") (pinfunction "P8_P$8") (pintype "bidirectional"))
      (node (ref "U6") (pin "E6") (pinfunction "1_E6") (pintype "bidirectional"))
    )
    (net (code "164") (name "PORTD3") (class "Default")
      (node (ref "J6") (pin "P$8") (pinfunction "P8_P$8") (pintype "bidirectional"))
      (node (ref "U6") (pin "C5") (pinfunction "1_C5") (pintype "bidirectional"))
    )
    (net (code "165") (name "PORTE0") (class "Default")
      (node (ref "J4") (pin "P$10") (pinfunction "P10_P$10") (pintype "bidirectional"))
      (node (ref "U6") (pin "D5") (pinfunction "1_D5") (pintype "bidirectional"))
    )
    (net (code "166") (name "PORTE1") (class "Default")
      (node (ref "J6") (pin "P$10") (pinfunction "P10_P$10") (pintype "bidirectional"))
      (node (ref "U6") (pin "A4") (pinfunction "1_A4") (pintype "bidirectional"))
    )
    (net (code "167") (name "PORTE2") (class "Default")
      (node (ref "J4") (pin "P$11") (pinfunction "P11_P$11") (pintype "bidirectional"))
      (node (ref "U6") (pin "G5") (pinfunction "1_G5") (pintype "bidirectional"))
    )
    (net (code "168") (name "PORTE3") (class "Default")
      (node (ref "J6") (pin "P$11") (pinfunction "P11_P$11") (pintype "bidirectional"))
      (node (ref "U6") (pin "A3") (pinfunction "1_A3") (pintype "bidirectional"))
    )
    (net (code "169") (name "PORTE4") (class "Default")
      (node (ref "J4") (pin "P$12") (pinfunction "P12_P$12") (pintype "bidirectional"))
      (node (ref "U6") (pin "B3") (pinfunction "1_B3") (pintype "bidirectional"))
    )
    (net (code "170") (name "PORTE5") (class "Default")
      (node (ref "J6") (pin "P$12") (pinfunction "P12_P$12") (pintype "bidirectional"))
      (node (ref "U6") (pin "A2") (pinfunction "1_A2") (pintype "bidirectional"))
    )
    (net (code "171") (name "PORTE6") (class "Default")
      (node (ref "J4") (pin "P$14") (pinfunction "P14_P$14") (pintype "bidirectional"))
      (node (ref "U6") (pin "B2") (pinfunction "1_B2") (pintype "bidirectional"))
    )
    (net (code "172") (name "PORTE7") (class "Default")
      (node (ref "J6") (pin "P$14") (pinfunction "P14_P$14") (pintype "bidirectional"))
      (node (ref "U6") (pin "C3") (pinfunction "1_C3") (pintype "bidirectional"))
    )
    (net (code "173") (name "PORTE8") (class "Default")
      (node (ref "J4") (pin "P$15") (pinfunction "P15_P$15") (pintype "bidirectional"))
      (node (ref "U6") (pin "C2") (pinfunction "1_C2") (pintype "bidirectional"))
    )
    (net (code "174") (name "PORTE9") (class "Default")
      (node (ref "J6") (pin "P$15") (pinfunction "P15_P$15") (pintype "bidirectional"))
      (node (ref "U6") (pin "D3") (pinfunction "1_D3") (pintype "bidirectional"))
    )
    (net (code "175") (name "PORTE10") (class "Default")
      (node (ref "J4") (pin "P$16") (pinfunction "P16_P$16") (pintype "bidirectional"))
      (node (ref "U6") (pin "D1") (pinfunction "1_D1") (pintype "bidirectional"))
    )
    (net (code "176") (name "PORTE11") (class "Default")
      (node (ref "J6") (pin "P$16") (pinfunction "P16_P$16") (pintype "bidirectional"))
      (node (ref "U6") (pin "E3") (pinfunction "1_E3") (pintype "bidirectional"))
    )
    (net (code "177") (name "PORTF0") (class "Default")
      (node (ref "J4") (pin "P$18") (pinfunction "P18_P$18") (pintype "bidirectional"))
      (node (ref "U6") (pin "E2") (pinfunction "1_E2") (pintype "bidirectional"))
    )
    (net (code "178") (name "PORTF1") (class "Default")
      (node (ref "J6") (pin "P$18") (pinfunction "P18_P$18") (pintype "bidirectional"))
      (node (ref "U6") (pin "E1") (pinfunction "1_E1") (pintype "bidirectional"))
    )
    (net (code "179") (name "PORTF2") (class "Default")
      (node (ref "J4") (pin "P$19") (pinfunction "P19_P$19") (pintype "bidirectional"))
      (node (ref "U6") (pin "E4") (pinfunction "1_E4") (pintype "bidirectional"))
    )
    (net (code "180") (name "PORTF3") (class "Default")
      (node (ref "J6") (pin "P$19") (pinfunction "P19_P$19") (pintype "bidirectional"))
      (node (ref "U6") (pin "F4") (pinfunction "1_F4") (pintype "bidirectional"))
    )
    (net (code "181") (name "PORTF4") (class "Default")
      (node (ref "J4") (pin "P$20") (pinfunction "P20_P$20") (pintype "bidirectional"))
      (node (ref "U6") (pin "F5") (pinfunction "1_F5") (pintype "bidirectional"))
    )
    (net (code "182") (name "PORTF5") (class "Default")
      (node (ref "J6") (pin "P$20") (pinfunction "P20_P$20") (pintype "bidirectional"))
      (node (ref "U6") (pin "G3") (pinfunction "1_G3") (pintype "bidirectional"))
    )
    (net (code "183") (name "PORTF6") (class "Default")
      (node (ref "J4") (pin "P$22") (pinfunction "P22_P$22") (pintype "bidirectional"))
      (node (ref "U6") (pin "F3") (pinfunction "1_F3") (pintype "bidirectional"))
    )
    (net (code "184") (name "PORTF7") (class "Default")
      (node (ref "J6") (pin "P$22") (pinfunction "P22_P$22") (pintype "bidirectional"))
      (node (ref "U6") (pin "G1") (pinfunction "1_G1") (pintype "bidirectional"))
    )
    (net (code "185") (name "PORTF8") (class "Default")
      (node (ref "J4") (pin "P$23") (pinfunction "P23_P$23") (pintype "bidirectional"))
      (node (ref "U6") (pin "H3") (pinfunction "1_H3") (pintype "bidirectional"))
    )
    (net (code "186") (name "PORTF9") (class "Default")
      (node (ref "J6") (pin "P$23") (pinfunction "P23_P$23") (pintype "bidirectional"))
      (node (ref "U6") (pin "H1") (pinfunction "1_H1") (pintype "bidirectional"))
    )
    (net (code "187") (name "PORTF10") (class "Default")
      (node (ref "J4") (pin "P$24") (pinfunction "P24_P$24") (pintype "bidirectional"))
      (node (ref "U6") (pin "H2") (pinfunction "1_H2") (pintype "bidirectional"))
    )
    (net (code "188") (name "PORTF11") (class "Default")
      (node (ref "J6") (pin "P$24") (pinfunction "P24_P$24") (pintype "bidirectional"))
      (node (ref "U6") (pin "J1") (pinfunction "1_J1") (pintype "bidirectional"))
    )
    (net (code "189") (name "RAS#") (class "Default")
      (node (ref "U6") (pin "R2") (pinfunction "1_R2") (pintype "bidirectional"))
      (node (ref "U9") (pin "18") (pinfunction "P$1_18") (pintype "bidirectional"))
    )
    (net (code "190") (name "REBOOT") (class "Default")
      (node (ref "R18") (pin "1") (pinfunction "1_1") (pintype "passive"))
      (node (ref "S1") (pin "3") (pinfunction "3_3") (pintype "passive"))
      (node (ref "S1") (pin "4") (pinfunction "4_4") (pintype "passive"))
      (node (ref "U6") (pin "T2") (pinfunction "1_T2") (pintype "input"))
    )
    (net (code "191") (name "SDRAM-CLK") (class "Default")
      (node (ref "U6") (pin "G16") (pinfunction "1_G16") (pintype "bidirectional"))
      (node (ref "U9") (pin "38") (pinfunction "P$1_38") (pintype "bidirectional"))
    )
    (net (code "192") (name "SDRAM-CS#") (class "Default")
      (node (ref "U6") (pin "R1") (pinfunction "1_R1") (pintype "bidirectional"))
      (node (ref "U9") (pin "19") (pinfunction "P$1_19") (pintype "bidirectional"))
    )
    (net (code "193") (name "SD_CD{slash}DAT3") (class "Default")
      (node (ref "J5") (pin "T2") (pinfunction "CD/DAT3_T2") (pintype "bidirectional"))
      (node (ref "U6") (pin "K12") (pinfunction "1_K12") (pintype "bidirectional"))
    )
    (net (code "194") (name "SD_CLK") (class "Default")
      (node (ref "J5") (pin "T5") (pinfunction "CLK_T5") (pintype "bidirectional"))
      (node (ref "U6") (pin "L12") (pinfunction "1_L12") (pintype "bidirectional"))
    )
    (net (code "195") (name "SD_CMD") (class "Default")
      (node (ref "J5") (pin "T3") (pinfunction "CMD_T3") (pintype "bidirectional"))
      (node (ref "U6") (pin "K11") (pinfunction "1_K11") (pintype "bidirectional"))
    )
    (net (code "196") (name "SD_DAT0") (class "Default")
      (node (ref "J5") (pin "T7") (pinfunction "DAT0_T7") (pintype "bidirectional"))
      (node (ref "U6") (pin "M10") (pinfunction "1_M10") (pintype "bidirectional"))
    )
    (net (code "197") (name "SD_DAT1") (class "Default")
      (node (ref "J5") (pin "T8") (pinfunction "DAT1_T8") (pintype "bidirectional"))
      (node (ref "U6") (pin "L10") (pinfunction "1_L10") (pintype "bidirectional"))
    )
    (net (code "198") (name "SD_DAT2") (class "Default")
      (node (ref "J5") (pin "T1") (pinfunction "DAT2_T1") (pintype "bidirectional"))
      (node (ref "U6") (pin "J11") (pinfunction "1_J11") (pintype "bidirectional"))
    )
    (net (code "199") (name "SW1") (class "Default")
      (node (ref "S2") (pin "8") (pinfunction "8_8") (pintype "passive"))
      (node (ref "U6") (pin "L1") (pinfunction "1_L1") (pintype "bidirectional"))
    )
    (net (code "200") (name "SW2") (class "Default")
      (node (ref "S2") (pin "7") (pinfunction "7_7") (pintype "passive"))
      (node (ref "U6") (pin "L3") (pinfunction "1_L3") (pintype "bidirectional"))
    )
    (net (code "201") (name "SW3") (class "Default")
      (node (ref "S2") (pin "6") (pinfunction "6_6") (pintype "passive"))
      (node (ref "U6") (pin "L4") (pinfunction "1_L4") (pintype "bidirectional"))
    )
    (net (code "202") (name "SW4") (class "Default")
      (node (ref "S2") (pin "5") (pinfunction "5_5") (pintype "passive"))
      (node (ref "U6") (pin "L5") (pinfunction "1_L5") (pintype "bidirectional"))
    )
    (net (code "203") (name "TCK") (class "Default")
      (node (ref "U2") (pin "16") (pinfunction "ADBUS0/TXD/TCK/SK_16") (pintype "bidirectional"))
      (node (ref "U6") (pin "C14") (pinfunction "1_C14") (pintype "input"))
    )
    (net (code "204") (name "TDI") (class "Default")
      (node (ref "U2") (pin "17") (pinfunction "ADBUS1/RXD/TDI/DO_17") (pintype "bidirectional"))
      (node (ref "U6") (pin "C12") (pinfunction "1_C12") (pintype "input"))
    )
    (net (code "205") (name "TDO") (class "Default")
      (node (ref "U2") (pin "18") (pinfunction "ADBUS2/RTS#/TDO/DI_18") (pintype "bidirectional"))
      (node (ref "U6") (pin "E14") (pinfunction "1_E14") (pintype "output"))
    )
    (net (code "206") (name "TMDS0_N") (class "Default")
      (node (ref "J2") (pin "9") (pinfunction "DATA0-_9") (pintype "bidirectional"))
      (node (ref "RN8") (pin "4") (pinfunction "2_4") (pintype "passive"))
      (node (ref "U6") (pin "A7") (pinfunction "1_A7") (pintype "bidirectional"))
    )
    (net (code "207") (name "TMDS0_P") (class "Default")
      (node (ref "J2") (pin "7") (pinfunction "DATA0+_7") (pintype "bidirectional"))
      (node (ref "RN8") (pin "2") (pinfunction "1_2") (pintype "passive"))
      (node (ref "U6") (pin "C7") (pinfunction "1_C7") (pintype "bidirectional"))
    )
    (net (code "208") (name "TMDS1_N") (class "Default")
      (node (ref "J2") (pin "6") (pinfunction "DATA1-_6") (pintype "bidirectional"))
      (node (ref "RN3") (pin "4") (pinfunction "2_4") (pintype "passive"))
      (node (ref "U6") (pin "A6") (pinfunction "1_A6") (pintype "bidirectional"))
    )
    (net (code "209") (name "TMDS1_P") (class "Default")
      (node (ref "J2") (pin "4") (pinfunction "DATA1+_4") (pintype "bidirectional"))
      (node (ref "RN3") (pin "2") (pinfunction "1_2") (pintype "passive"))
      (node (ref "U6") (pin "B6") (pinfunction "1_B6") (pintype "bidirectional"))
    )
    (net (code "210") (name "TMDS2_N") (class "Default")
      (node (ref "J2") (pin "3") (pinfunction "DATA2-_3") (pintype "bidirectional"))
      (node (ref "RN4") (pin "4") (pinfunction "2_4") (pintype "passive"))
      (node (ref "U6") (pin "A5") (pinfunction "1_A5") (pintype "bidirectional"))
    )
    (net (code "211") (name "TMDS2_P") (class "Default")
      (node (ref "J2") (pin "1") (pinfunction "DATA2+_1") (pintype "bidirectional"))
      (node (ref "RN4") (pin "2") (pinfunction "1_2") (pintype "passive"))
      (node (ref "U6") (pin "B5") (pinfunction "1_B5") (pintype "bidirectional"))
    )
    (net (code "212") (name "TMDS_CLK_N") (class "Default")
      (node (ref "J2") (pin "12") (pinfunction "CLOCK-_12") (pintype "bidirectional"))
      (node (ref "RN9") (pin "4") (pinfunction "2_4") (pintype "passive"))
      (node (ref "U6") (pin "A9") (pinfunction "1_A9") (pintype "bidirectional"))
    )
    (net (code "213") (name "TMDS_CLK_P") (class "Default")
      (node (ref "J2") (pin "10") (pinfunction "CLOCK+_10") (pintype "bidirectional"))
      (node (ref "RN9") (pin "2") (pinfunction "1_2") (pintype "passive"))
      (node (ref "U6") (pin "C9") (pinfunction "1_C9") (pintype "bidirectional"))
    )
    (net (code "214") (name "TMS") (class "Default")
      (node (ref "U2") (pin "19") (pinfunction "ADBUS3/CTS#/TMS/CS_19") (pintype "bidirectional"))
      (node (ref "U6") (pin "A15") (pinfunction "1_A15") (pintype "input"))
    )
    (net (code "215") (name "TX_HDMI_5V") (class "Default")
      (node (ref "J2") (pin "18") (pinfunction "+5V_18") (pintype "bidirectional"))
      (node (ref "R14") (pin "1") (pinfunction "1_1") (pintype "passive"))
      (node (ref "R6") (pin "1") (pinfunction "1_1") (pintype "passive"))
      (node (ref "RN5") (pin "3") (pinfunction "1_3") (pintype "passive"))
      (node (ref "RN5") (pin "4") (pinfunction "1_4") (pintype "passive"))
    )
    (net (code "216") (name "UDQM") (class "Default")
      (node (ref "U6") (pin "F15") (pinfunction "1_F15") (pintype "bidirectional"))
      (node (ref "U9") (pin "39") (pinfunction "P$1_39") (pintype "bidirectional"))
    )
    (net (code "217") (name "VCORE") (class "Default")
      (node (ref "C2") (pin "1") (pinfunction "1_1") (pintype "passive"))
      (node (ref "C4") (pin "1") (pinfunction "1_1") (pintype "passive"))
      (node (ref "C7") (pin "1") (pinfunction "1_1") (pintype "passive"))
      (node (ref "C9") (pin "1") (pinfunction "1_1") (pintype "passive"))
      (node (ref "U2") (pin "12") (pinfunction "VCORE0_12") (pintype "bidirectional"))
      (node (ref "U2") (pin "37") (pinfunction "VCORE1_37") (pintype "bidirectional"))
      (node (ref "U2") (pin "49") (pinfunction "VREGOUT_49") (pintype "bidirectional"))
      (node (ref "U2") (pin "64") (pinfunction "VCORE2_64") (pintype "bidirectional"))
    )
    (net (code "218") (name "WE#") (class "Default")
      (node (ref "U6") (pin "R5") (pinfunction "1_R5") (pintype "bidirectional"))
      (node (ref "U9") (pin "16") (pinfunction "P$1_16") (pintype "bidirectional"))
    )
    (net (code "219") (name "unconnected-(J2-CEC-Pad13)") (class "Default")
      (node (ref "J2") (pin "13") (pinfunction "CEC_13") (pintype "bidirectional"))
    )
    (net (code "220") (name "unconnected-(J3-+5V-Pad18)") (class "Default")
      (node (ref "J3") (pin "18") (pinfunction "+5V_18") (pintype "bidirectional"))
    )
    (net (code "221") (name "unconnected-(J3-CEC-Pad13)") (class "Default")
      (node (ref "J3") (pin "13") (pinfunction "CEC_13") (pintype "bidirectional"))
    )
    (net (code "222") (name "unconnected-(J3-SCL-Pad15)") (class "Default")
      (node (ref "J3") (pin "15") (pinfunction "SCL_15") (pintype "bidirectional"))
    )
    (net (code "223") (name "unconnected-(J3-SDA-Pad16)") (class "Default")
      (node (ref "J3") (pin "16") (pinfunction "SDA_16") (pintype "bidirectional"))
    )
    (net (code "224") (name "unconnected-(J5-PadS1)") (class "Default")
      (node (ref "J5") (pin "S1") (pinfunction "S1_S1") (pintype "bidirectional"))
    )
    (net (code "225") (name "unconnected-(J5-PadS2)") (class "Default")
      (node (ref "J5") (pin "S2") (pinfunction "S2_S2") (pintype "bidirectional"))
    )
    (net (code "226") (name "unconnected-(JP5-PadRING2)") (class "Default")
      (node (ref "JP5") (pin "RING2") (pinfunction "RING2_RING2") (pintype "bidirectional"))
    )
    (net (code "227") (name "unconnected-(U2-ACBUS0{slash}TXDEN{slash}GPIOH0-Pad26)") (class "Default")
      (node (ref "U2") (pin "26") (pinfunction "ACBUS0/TXDEN/GPIOH0_26") (pintype "bidirectional"))
    )
    (net (code "228") (name "unconnected-(U2-ACBUS1{slash}GPIOH1-Pad27)") (class "Default")
      (node (ref "U2") (pin "27") (pinfunction "ACBUS1/GPIOH1_27") (pintype "bidirectional"))
    )
    (net (code "229") (name "unconnected-(U2-ACBUS2{slash}GPIOH2-Pad28)") (class "Default")
      (node (ref "U2") (pin "28") (pinfunction "ACBUS2/GPIOH2_28") (pintype "bidirectional"))
    )
    (net (code "230") (name "unconnected-(U2-ACBUS3{slash}RXLED#{slash}GPIOH3-Pad29)") (class "Default")
      (node (ref "U2") (pin "29") (pinfunction "ACBUS3/RXLED#/GPIOH3_29") (pintype "bidirectional"))
    )
    (net (code "231") (name "unconnected-(U2-ACBUS4{slash}TXLED#{slash}GPIOH4-Pad30)") (class "Default")
      (node (ref "U2") (pin "30") (pinfunction "ACBUS4/TXLED#/GPIOH4_30") (pintype "bidirectional"))
    )
    (net (code "232") (name "unconnected-(U2-ACBUS5{slash}GPIOH5-Pad32)") (class "Default")
      (node (ref "U2") (pin "32") (pinfunction "ACBUS5/GPIOH5_32") (pintype "bidirectional"))
    )
    (net (code "233") (name "unconnected-(U2-ACBUS6{slash}GPIOH6-Pad33)") (class "Default")
      (node (ref "U2") (pin "33") (pinfunction "ACBUS6/GPIOH6_33") (pintype "bidirectional"))
    )
    (net (code "234") (name "unconnected-(U2-ACBUS7{slash}GPIOH7-Pad34)") (class "Default")
      (node (ref "U2") (pin "34") (pinfunction "ACBUS7/GPIOH7_34") (pintype "bidirectional"))
    )
    (net (code "235") (name "unconnected-(U2-ADBUS4{slash}DTR#{slash}GPIOL0-Pad21)") (class "Default")
      (node (ref "U2") (pin "21") (pinfunction "ADBUS4/DTR#/GPIOL0_21") (pintype "bidirectional"))
    )
    (net (code "236") (name "unconnected-(U2-ADBUS5{slash}DSR#{slash}GPIOL1-Pad22)") (class "Default")
      (node (ref "U2") (pin "22") (pinfunction "ADBUS5/DSR#/GPIOL1_22") (pintype "bidirectional"))
    )
    (net (code "237") (name "unconnected-(U2-ADBUS6{slash}DCD#{slash}GPIOL2-Pad23)") (class "Default")
      (node (ref "U2") (pin "23") (pinfunction "ADBUS6/DCD#/GPIOL2_23") (pintype "bidirectional"))
    )
    (net (code "238") (name "unconnected-(U2-ADBUS7{slash}RI#{slash}GPIOL3-Pad24)") (class "Default")
      (node (ref "U2") (pin "24") (pinfunction "ADBUS7/RI#/GPIOL3_24") (pintype "bidirectional"))
    )
    (net (code "239") (name "unconnected-(U2-BCBUS5{slash}GPIOH5-Pad57)") (class "Default")
      (node (ref "U2") (pin "57") (pinfunction "BCBUS5/GPIOH5_57") (pintype "bidirectional"))
    )
    (net (code "240") (name "unconnected-(U2-BCBUS6{slash}GPIOH6-Pad58)") (class "Default")
      (node (ref "U2") (pin "58") (pinfunction "BCBUS6/GPIOH6_58") (pintype "bidirectional"))
    )
    (net (code "241") (name "unconnected-(U2-BCBUS7{slash}GPIOH7-Pad59)") (class "Default")
      (node (ref "U2") (pin "59") (pinfunction "BCBUS7/GPIOH7_59") (pintype "bidirectional"))
    )
    (net (code "242") (name "unconnected-(U2-PWREN#-Pad60)") (class "Default")
      (node (ref "U2") (pin "60") (pinfunction "PWREN#_60") (pintype "bidirectional"))
    )
    (net (code "243") (name "unconnected-(U2-SUSPEND#-Pad36)") (class "Default")
      (node (ref "U2") (pin "36") (pinfunction "SUSPEND#_36") (pintype "bidirectional"))
    )
    (net (code "244") (name "unconnected-(U6A-1-PadL11)") (class "Default")
      (node (ref "U6") (pin "L11") (pinfunction "1_L11") (pintype "input"))
    )
    (net (code "245") (name "unconnected-(U6AO-1-PadM4)") (class "Default")
      (node (ref "U6") (pin "M4") (pinfunction "1_M4") (pintype "bidirectional"))
    )
    (net (code "246") (name "unconnected-(U6AZ-1-PadN4)") (class "Default")
      (node (ref "U6") (pin "N4") (pinfunction "1_N4") (pintype "bidirectional"))
    )
    (net (code "247") (name "unconnected-(U6BC-1-PadM5)") (class "Default")
      (node (ref "U6") (pin "M5") (pinfunction "1_M5") (pintype "bidirectional"))
    )
    (net (code "248") (name "unconnected-(U6BE-1-PadG11)") (class "Default")
      (node (ref "U6") (pin "G11") (pinfunction "1_G11") (pintype "bidirectional"))
    )
    (net (code "249") (name "unconnected-(U6CS-1-PadK1)") (class "Default")
      (node (ref "U6") (pin "K1") (pinfunction "1_K1") (pintype "bidirectional"))
    )
    (net (code "250") (name "unconnected-(U6CV-1-PadK2)") (class "Default")
      (node (ref "U6") (pin "K2") (pinfunction "1_K2") (pintype "bidirectional"))
    )
    (net (code "251") (name "unconnected-(U6CW-1-PadH11)") (class "Default")
      (node (ref "U6") (pin "H11") (pinfunction "1_H11") (pintype "bidirectional"))
    )
    (net (code "252") (name "unconnected-(U6DB-1-PadJ3)") (class "Default")
      (node (ref "U6") (pin "J3") (pinfunction "1_J3") (pintype "bidirectional"))
    )
    (net (code "253") (name "unconnected-(U6DG-1-PadH13)") (class "Default")
      (node (ref "U6") (pin "H13") (pinfunction "1_H13") (pintype "bidirectional"))
    )
    (net (code "254") (name "unconnected-(U6DS-1-PadF1)") (class "Default")
      (node (ref "U6") (pin "F1") (pinfunction "1_F1") (pintype "bidirectional"))
    )
    (net (code "255") (name "unconnected-(U6DU-1-PadF2)") (class "Default")
      (node (ref "U6") (pin "F2") (pinfunction "1_F2") (pintype "bidirectional"))
    )
    (net (code "256") (name "unconnected-(U6EC-1-PadJ6)") (class "Default")
      (node (ref "U6") (pin "J6") (pinfunction "1_J6") (pintype "bidirectional"))
    )
    (net (code "257") (name "unconnected-(U6ES-1-PadK6)") (class "Default")
      (node (ref "U6") (pin "K6") (pinfunction "1_K6") (pintype "bidirectional"))
    )
    (net (code "258") (name "unconnected-(U6ET-1-PadP6)") (class "Default")
      (node (ref "U6") (pin "P6") (pinfunction "1_P6") (pintype "bidirectional"))
    )
    (net (code "259") (name "unconnected-(U6EV-1-PadK5)") (class "Default")
      (node (ref "U6") (pin "K5") (pinfunction "1_K5") (pintype "bidirectional"))
    )
    (net (code "260") (name "unconnected-(U6GF-1-PadF7)") (class "Default")
      (node (ref "U6") (pin "F7") (pinfunction "1_F7") (pintype "bidirectional"))
    )
    (net (code "261") (name "unconnected-(U6GG-1-PadL7)") (class "Default")
      (node (ref "U6") (pin "L7") (pinfunction "1_L7") (pintype "bidirectional"))
    )
    (net (code "262") (name "unconnected-(U6GJ-1-PadL8)") (class "Default")
      (node (ref "U6") (pin "L8") (pinfunction "1_L8") (pintype "bidirectional"))
    )
    (net (code "263") (name "unconnected-(U9AK-P$1-Pad40)") (class "Default")
      (node (ref "U9") (pin "40") (pinfunction "P$1_40") (pintype "bidirectional"))
    )
    (net (code "264") (name "unconnected-(X1-Pad4)") (class "Default")
      (node (ref "X1") (pin "4") (pinfunction "4_4") (pintype "input"))
    )
  )
)
